# EPS32-v2.net
KiCad netlist of a schematic drawn in EasyEDA Pro
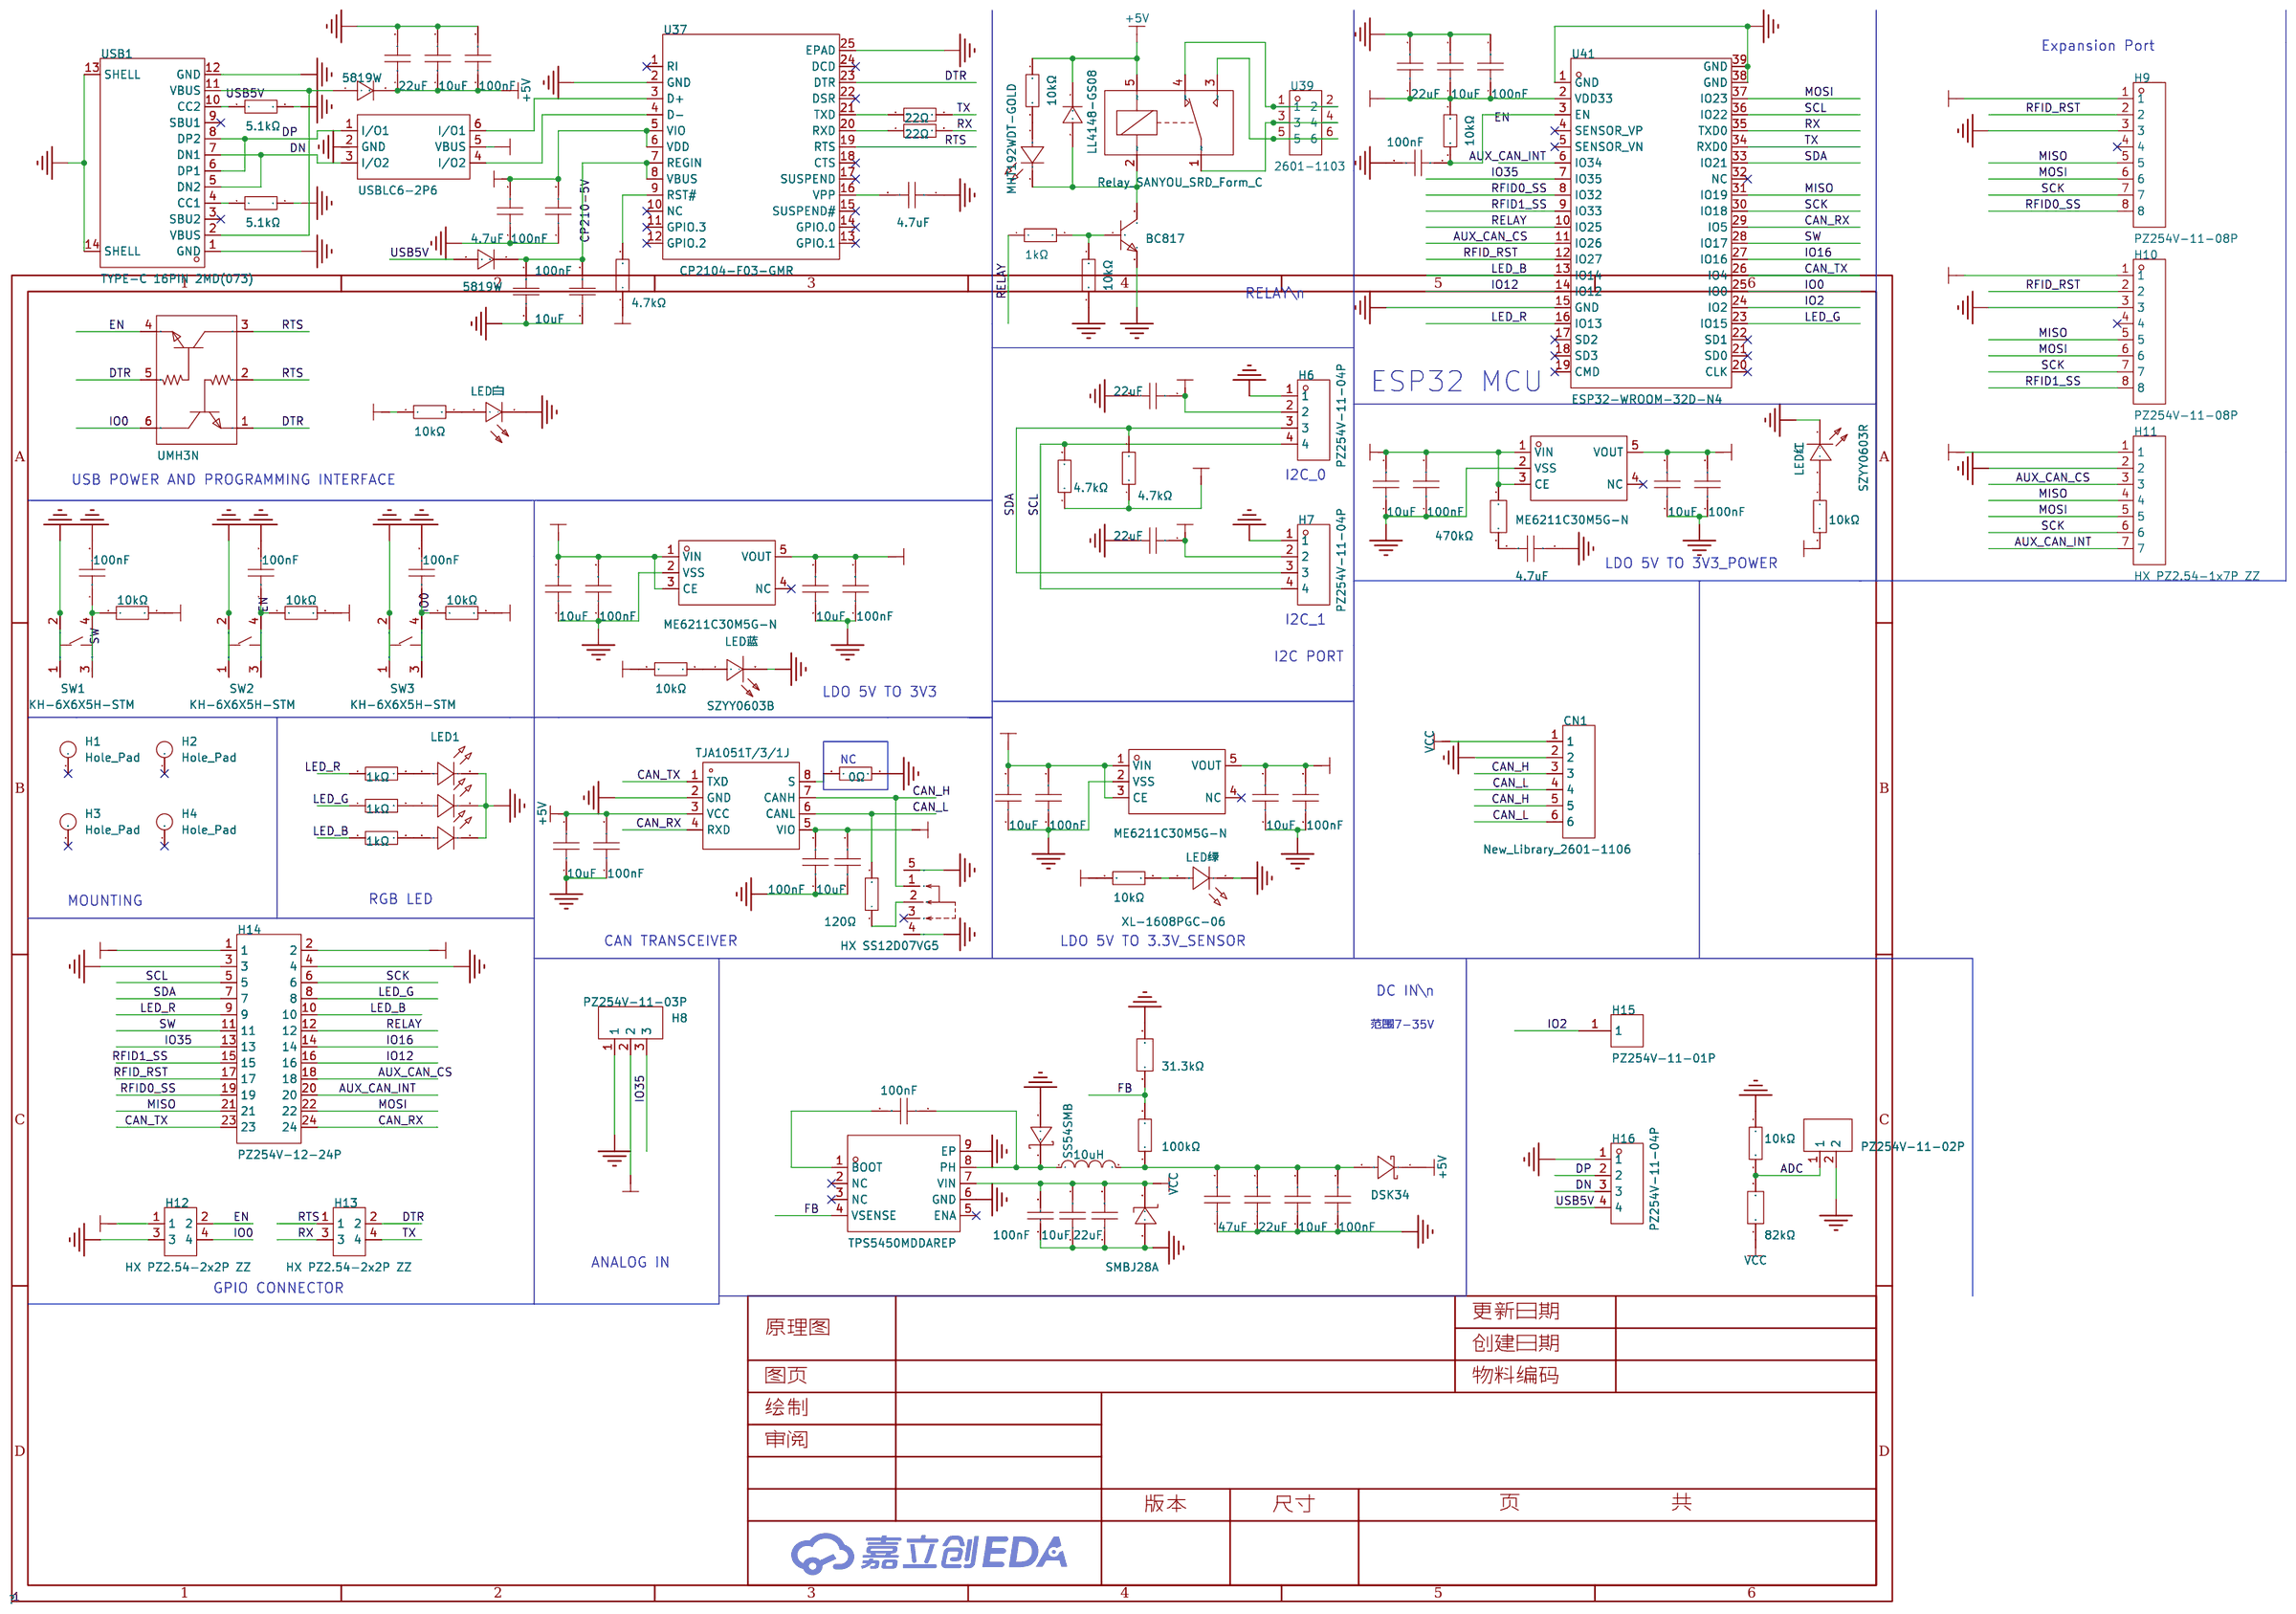
[diagram p0: schematic sheet]

(export (version "E")
  (design (tool "Eeschema 10.0.6"))
  (components
    (comp (ref "C1")
      (value "22uF")
      (footprint "easyedapro:C0805")
      (description "容值:22uF;精度:±20%;额定电压:35V;材质(温度系数):X5R;")
      (fields
        (field (name "Manufacturer Part") "CGA0805X5R226M350MT")
        (field (name "Manufacturer") "HRE(芯声)")
      )
      (libsource (lib "easyedapro") (part "CGA0805X5R226M350MT"))
    )
    (comp (ref "C2")
      (value "10uF")
      (footprint "easyedapro:C0603")
      (description "容值:10uF;精度:±20%;额定电压:25V;材质(温度系数):X5R;")
      (fields
        (field (name "Manufacturer Part") "CL10A106MA8NRNC")
        (field (name "Manufacturer") "SAMSUNG(三星)")
      )
      (libsource (lib "easyedapro") (part "CL10A106MA8NRNC"))
    )
    (comp (ref "C3")
      (value "100nF")
      (footprint "easyedapro:C0603")
      (description "容值:100nF;精度:±10%;额定电压:50V;温度系数:X7R;")
      (fields
        (field (name "Manufacturer Part") "CGA0603X7R104K500JT")
        (field (name "Manufacturer") "HRE(芯声)")
      )
      (libsource (lib "easyedapro") (part "CGA0603X7R104K500JT"))
    )
    (comp (ref "C6")
      (value "4.7uF")
      (footprint "easyedapro:C0603")
      (description "容值:4.7uF;精度:±10%;额定电压:25V;温度系数:X5R;")
      (fields
        (field (name "Manufacturer Part") "CGA0603X5R475K250JT")
        (field (name "Manufacturer") "HRE(芯声)")
      )
      (libsource (lib "easyedapro") (part "CGA0603X5R475K250JT"))
    )
    (comp (ref "C9")
      (value "100nF")
      (footprint "easyedapro:C0603")
      (description "容值:100nF;精度:±10%;额定电压:50V;温度系数:X7R;")
      (fields
        (field (name "Manufacturer Part") "CGA0603X7R104K500JT")
        (field (name "Manufacturer") "HRE(芯声)")
      )
      (libsource (lib "easyedapro") (part "CGA0603X7R104K500JT"))
    )
    (comp (ref "C10")
      (value "100nF")
      (footprint "easyedapro:C0603")
      (description "容值:100nF;精度:±10%;额定电压:50V;温度系数:X7R;")
      (fields
        (field (name "Manufacturer Part") "CGA0603X7R104K500JT")
        (field (name "Manufacturer") "HRE(芯声)")
      )
      (libsource (lib "easyedapro") (part "CGA0603X7R104K500JT"))
    )
    (comp (ref "C11")
      (value "100nF")
      (footprint "easyedapro:C0603")
      (description "容值:100nF;精度:±10%;额定电压:50V;温度系数:X7R;")
      (fields
        (field (name "Manufacturer Part") "CGA0603X7R104K500JT")
        (field (name "Manufacturer") "HRE(芯声)")
      )
      (libsource (lib "easyedapro") (part "CGA0603X7R104K500JT"))
    )
    (comp (ref "C351")
      (value "10uF")
      (footprint "easyedapro:C0603")
      (description "容值:10uF;精度:±20%;额定电压:25V;材质(温度系数):X5R;")
      (fields
        (field (name "Manufacturer Part") "CL10A106MA8NRNC")
        (field (name "Manufacturer") "SAMSUNG(三星)")
      )
      (libsource (lib "easyedapro") (part "CL10A106MA8NRNC"))
    )
    (comp (ref "C352")
      (value "10uF")
      (footprint "easyedapro:C0603")
      (description "容值:10uF;精度:±20%;额定电压:25V;材质(温度系数):X5R;")
      (fields
        (field (name "Manufacturer Part") "CL10A106MA8NRNC")
        (field (name "Manufacturer") "SAMSUNG(三星)")
      )
      (libsource (lib "easyedapro") (part "CL10A106MA8NRNC"))
    )
    (comp (ref "C353")
      (value "100nF")
      (footprint "easyedapro:C0603")
      (description "容值:100nF;精度:±10%;额定电压:50V;温度系数:X7R;")
      (fields
        (field (name "Manufacturer Part") "CGA0603X7R104K500JT")
        (field (name "Manufacturer") "HRE(芯声)")
      )
      (libsource (lib "easyedapro") (part "CGA0603X7R104K500JT"))
    )
    (comp (ref "C354")
      (value "100nF")
      (footprint "easyedapro:C0603")
      (description "容值:100nF;精度:±10%;额定电压:50V;温度系数:X7R;")
      (fields
        (field (name "Manufacturer Part") "CGA0603X7R104K500JT")
        (field (name "Manufacturer") "HRE(芯声)")
      )
      (libsource (lib "easyedapro") (part "CGA0603X7R104K500JT"))
    )
    (comp (ref "C355")
      (value "10uF")
      (footprint "easyedapro:C0603")
      (description "容值:10uF;精度:±20%;额定电压:25V;材质(温度系数):X5R;")
      (fields
        (field (name "Manufacturer Part") "CL10A106MA8NRNC")
        (field (name "Manufacturer") "SAMSUNG(三星)")
      )
      (libsource (lib "easyedapro") (part "CL10A106MA8NRNC"))
    )
    (comp (ref "C356")
      (value "100nF")
      (footprint "easyedapro:C0603")
      (description "容值:100nF;精度:±10%;额定电压:50V;温度系数:X7R;")
      (fields
        (field (name "Manufacturer Part") "CGA0603X7R104K500JT")
        (field (name "Manufacturer") "HRE(芯声)")
      )
      (libsource (lib "easyedapro") (part "CGA0603X7R104K500JT"))
    )
    (comp (ref "C357")
      (value "10uF")
      (footprint "easyedapro:C0603")
      (description "容值:10uF;精度:±20%;额定电压:25V;材质(温度系数):X5R;")
      (fields
        (field (name "Manufacturer Part") "CL10A106MA8NRNC")
        (field (name "Manufacturer") "SAMSUNG(三星)")
      )
      (libsource (lib "easyedapro") (part "CL10A106MA8NRNC"))
    )
    (comp (ref "C358")
      (value "100nF")
      (footprint "easyedapro:C0603")
      (description "容值:100nF;精度:±10%;额定电压:50V;温度系数:X7R;")
      (fields
        (field (name "Manufacturer Part") "CGA0603X7R104K500JT")
        (field (name "Manufacturer") "HRE(芯声)")
      )
      (libsource (lib "easyedapro") (part "CGA0603X7R104K500JT"))
    )
    (comp (ref "C359")
      (value "100nF")
      (footprint "easyedapro:C0603")
      (description "容值:100nF;精度:±10%;额定电压:50V;温度系数:X7R;")
      (fields
        (field (name "Manufacturer Part") "CGA0603X7R104K500JT")
        (field (name "Manufacturer") "HRE(芯声)")
      )
      (libsource (lib "easyedapro") (part "CGA0603X7R104K500JT"))
    )
    (comp (ref "C360")
      (value "4.7uF")
      (footprint "easyedapro:C0603")
      (description "容值:4.7uF;精度:±10%;额定电压:25V;温度系数:X5R;")
      (fields
        (field (name "Manufacturer Part") "CGA0603X5R475K250JT")
        (field (name "Manufacturer") "HRE(芯声)")
      )
      (libsource (lib "easyedapro") (part "CGA0603X5R475K250JT"))
    )
    (comp (ref "C361")
      (value "10uF")
      (footprint "easyedapro:C0603")
      (description "容值:10uF;精度:±20%;额定电压:25V;材质(温度系数):X5R;")
      (fields
        (field (name "Manufacturer Part") "CL10A106MA8NRNC")
        (field (name "Manufacturer") "SAMSUNG(三星)")
      )
      (libsource (lib "easyedapro") (part "CL10A106MA8NRNC"))
    )
    (comp (ref "C362")
      (value "100nF")
      (footprint "easyedapro:C0603")
      (description "容值:100nF;精度:±10%;额定电压:50V;温度系数:X7R;")
      (fields
        (field (name "Manufacturer Part") "CGA0603X7R104K500JT")
        (field (name "Manufacturer") "HRE(芯声)")
      )
      (libsource (lib "easyedapro") (part "CGA0603X7R104K500JT"))
    )
    (comp (ref "C363")
      (value "22uF")
      (footprint "easyedapro:C0805")
      (description "容值:22uF;精度:±20%;额定电压:35V;材质(温度系数):X5R;")
      (fields
        (field (name "Manufacturer Part") "CGA0805X5R226M350MT")
        (field (name "Manufacturer") "HRE(芯声)")
      )
      (libsource (lib "easyedapro") (part "CGA0805X5R226M350MT"))
    )
    (comp (ref "C364")
      (value "22uF")
      (footprint "easyedapro:C0805")
      (description "容值:22uF;精度:±20%;额定电压:35V;材质(温度系数):X5R;")
      (fields
        (field (name "Manufacturer Part") "CGA0805X5R226M350MT")
        (field (name "Manufacturer") "HRE(芯声)")
      )
      (libsource (lib "easyedapro") (part "CGA0805X5R226M350MT"))
    )
    (comp (ref "C369")
      (value "10uF")
      (footprint "easyedapro:C0603")
      (description "容值:10uF;精度:±20%;额定电压:25V;材质(温度系数):X5R;")
      (fields
        (field (name "Manufacturer Part") "CL10A106MA8NRNC")
        (field (name "Manufacturer") "SAMSUNG(三星)")
      )
      (libsource (lib "easyedapro") (part "CL10A106MA8NRNC"))
    )
    (comp (ref "C370")
      (value "10uF")
      (footprint "easyedapro:C0603")
      (description "容值:10uF;精度:±20%;额定电压:25V;材质(温度系数):X5R;")
      (fields
        (field (name "Manufacturer Part") "CL10A106MA8NRNC")
        (field (name "Manufacturer") "SAMSUNG(三星)")
      )
      (libsource (lib "easyedapro") (part "CL10A106MA8NRNC"))
    )
    (comp (ref "C371")
      (value "100nF")
      (footprint "easyedapro:C0603")
      (description "容值:100nF;精度:±10%;额定电压:50V;温度系数:X7R;")
      (fields
        (field (name "Manufacturer Part") "CGA0603X7R104K500JT")
        (field (name "Manufacturer") "HRE(芯声)")
      )
      (libsource (lib "easyedapro") (part "CGA0603X7R104K500JT"))
    )
    (comp (ref "C372")
      (value "100nF")
      (footprint "easyedapro:C0603")
      (description "容值:100nF;精度:±10%;额定电压:50V;温度系数:X7R;")
      (fields
        (field (name "Manufacturer Part") "CGA0603X7R104K500JT")
        (field (name "Manufacturer") "HRE(芯声)")
      )
      (libsource (lib "easyedapro") (part "CGA0603X7R104K500JT"))
    )
    (comp (ref "C373")
      (value "10uF")
      (footprint "easyedapro:C0603")
      (description "容值:10uF;精度:±20%;额定电压:25V;材质(温度系数):X5R;")
      (fields
        (field (name "Manufacturer Part") "CL10A106MA8NRNC")
        (field (name "Manufacturer") "SAMSUNG(三星)")
      )
      (libsource (lib "easyedapro") (part "CL10A106MA8NRNC"))
    )
    (comp (ref "C374")
      (value "100nF")
      (footprint "easyedapro:C0603")
      (description "容值:100nF;精度:±10%;额定电压:50V;温度系数:X7R;")
      (fields
        (field (name "Manufacturer Part") "CGA0603X7R104K500JT")
        (field (name "Manufacturer") "HRE(芯声)")
      )
      (libsource (lib "easyedapro") (part "CGA0603X7R104K500JT"))
    )
    (comp (ref "C375")
      (value "100nF")
      (footprint "easyedapro:C0603")
      (description "容值:100nF;精度:±10%;额定电压:50V;温度系数:X7R;")
      (fields
        (field (name "Manufacturer Part") "CGA0603X7R104K500JT")
        (field (name "Manufacturer") "HRE(芯声)")
      )
      (libsource (lib "easyedapro") (part "CGA0603X7R104K500JT"))
    )
    (comp (ref "C376")
      (value "10uF")
      (footprint "easyedapro:C0603")
      (description "容值:10uF;精度:±20%;额定电压:25V;材质(温度系数):X5R;")
      (fields
        (field (name "Manufacturer Part") "CL10A106MA8NRNC")
        (field (name "Manufacturer") "SAMSUNG(三星)")
      )
      (libsource (lib "easyedapro") (part "CL10A106MA8NRNC"))
    )
    (comp (ref "C377")
      (value "22uF")
      (footprint "easyedapro:C0805")
      (description "容值:22uF;精度:±20%;额定电压:35V;材质(温度系数):X5R;")
      (fields
        (field (name "Manufacturer Part") "CGA0805X5R226M350MT")
        (field (name "Manufacturer") "HRE(芯声)")
      )
      (libsource (lib "easyedapro") (part "CGA0805X5R226M350MT"))
    )
    (comp (ref "C378")
      (value "10uF")
      (footprint "easyedapro:C0603")
      (description "容值:10uF;精度:±20%;额定电压:25V;材质(温度系数):X5R;")
      (fields
        (field (name "Manufacturer Part") "CL10A106MA8NRNC")
        (field (name "Manufacturer") "SAMSUNG(三星)")
      )
      (libsource (lib "easyedapro") (part "CL10A106MA8NRNC"))
    )
    (comp (ref "C379")
      (value "100nF")
      (footprint "easyedapro:C0603")
      (description "容值:100nF;精度:±10%;额定电压:50V;温度系数:X7R;")
      (fields
        (field (name "Manufacturer Part") "CGA0603X7R104K500JT")
        (field (name "Manufacturer") "HRE(芯声)")
      )
      (libsource (lib "easyedapro") (part "CGA0603X7R104K500JT"))
    )
    (comp (ref "C380")
      (value "100nF")
      (footprint "easyedapro:C0603")
      (description "容值:100nF;精度:±10%;额定电压:50V;温度系数:X7R;")
      (fields
        (field (name "Manufacturer Part") "CGA0603X7R104K500JT")
        (field (name "Manufacturer") "HRE(芯声)")
      )
      (libsource (lib "easyedapro") (part "CGA0603X7R104K500JT"))
    )
    (comp (ref "C382")
      (value "10uF")
      (footprint "easyedapro:C1206")
      (description "容值:10uF;精度:±10%;额定电压:50V;温度系数:X5R;")
      (fields
        (field (name "Manufacturer Part") "HGC1206R5106K500NSPJ")
        (field (name "Manufacturer") "Chinocera(华瓷)")
      )
      (libsource (lib "easyedapro") (part "HGC1206R5106K500NSPJ"))
    )
    (comp (ref "C383")
      (value "22uF")
      (footprint "easyedapro:C1206")
      (description "容值:22uF;精度:±20%;额定电压:35V;温度系数:X5R;")
      (fields
        (field (name "Manufacturer Part") "CGA1206X5R226M350NT")
        (field (name "Manufacturer") "HRE(芯声)")
      )
      (libsource (lib "easyedapro") (part "CGA1206X5R226M350NT"))
    )
    (comp (ref "C384")
      (value "100nF")
      (footprint "easyedapro:C1206")
      (description "容值:100nF;精度:±10%;额定电压:50V;材质(温度系数):X7R;")
      (fields
        (field (name "Manufacturer Part") "CL31B104KBCNNNC")
        (field (name "Manufacturer") "SAMSUNG(三星)")
      )
      (libsource (lib "easyedapro") (part "CL31B104KBCNNNC"))
    )
    (comp (ref "C385")
      (value "47uF")
      (footprint "easyedapro:C1206")
      (description "容值:47uF;精度:±20%;额定电压:25V;温度系数:X5R;")
      (fields
        (field (name "Manufacturer Part") "HGC1206R5476M250NSPJ")
        (field (name "Manufacturer") "Chinocera(华瓷)")
      )
      (libsource (lib "easyedapro") (part "HGC1206R5476M250NSPJ"))
    )
    (comp (ref "C386")
      (value "22uF")
      (footprint "easyedapro:C0805")
      (description "容值:22uF;精度:±20%;额定电压:35V;材质(温度系数):X5R;")
      (fields
        (field (name "Manufacturer Part") "CGA0805X5R226M350MT")
        (field (name "Manufacturer") "HRE(芯声)")
      )
      (libsource (lib "easyedapro") (part "CGA0805X5R226M350MT"))
    )
    (comp (ref "C387")
      (value "10uF")
      (footprint "easyedapro:C0603")
      (description "容值:10uF;精度:±20%;额定电压:25V;材质(温度系数):X5R;")
      (fields
        (field (name "Manufacturer Part") "CL10A106MA8NRNC")
        (field (name "Manufacturer") "SAMSUNG(三星)")
      )
      (libsource (lib "easyedapro") (part "CL10A106MA8NRNC"))
    )
    (comp (ref "C388")
      (value "100nF")
      (footprint "easyedapro:C0603")
      (description "容值:100nF;精度:±10%;额定电压:50V;温度系数:X7R;")
      (fields
        (field (name "Manufacturer Part") "CGA0603X7R104K500JT")
        (field (name "Manufacturer") "HRE(芯声)")
      )
      (libsource (lib "easyedapro") (part "CGA0603X7R104K500JT"))
    )
    (comp (ref "C389")
      (value "100nF")
      (footprint "easyedapro:C0603")
      (description "容值:100nF;精度:±10%;额定电压:50V;温度系数:X7R;")
      (fields
        (field (name "Manufacturer Part") "CGA0603X7R104K500JT")
        (field (name "Manufacturer") "HRE(芯声)")
      )
      (libsource (lib "easyedapro") (part "CGA0603X7R104K500JT"))
    )
    (comp (ref "C390")
      (value "4.7uF")
      (footprint "easyedapro:C0603")
      (description "容值:4.7uF;精度:±10%;额定电压:25V;温度系数:X5R;")
      (fields
        (field (name "Manufacturer Part") "CGA0603X5R475K250JT")
        (field (name "Manufacturer") "HRE(芯声)")
      )
      (libsource (lib "easyedapro") (part "CGA0603X5R475K250JT"))
    )
    (comp (ref "CN1")
      (value "New_Library_2601-1106")
      (footprint "easyedapro:CONN-TH_2601-1106")
      (fields (field (name "Manufacturer Part") "2601-1106"))
      (libsource (lib "easyedapro") (part "2601-1106"))
    )
    (comp (ref "D1")
      (value "USBLC6-2P6")
      (footprint "easyedapro:SOT-666-6_L1.6-W1.2-P0.50-LS1.6-BL")
      (description "极性:单向;反向截止电压(Vrwm):5V;最大钳位电压:14V;峰值脉冲电流(Ipp):5.5A;峰值脉冲功率(Ppp):80W;击穿电压:6V;")
      (fields (field (name "Manufacturer") "TECH PUBLIC(台舟)"))
      (libsource (lib "easyedapro") (part "USBLC6-2P6_C2827693"))
    )
    (comp (ref "D2")
      (value "5819W")
      (footprint "easyedapro:SOD-123_L2.7-W1.6-LS3.7-FD")
      (description "正向压降(Vf):900mV@3A;直流反向耐压(Vr):40V;整流电流:1A;")
      (fields (field (name "Manufacturer") "MOT(仁懋)"))
      (libsource (lib "easyedapro") (part "5819W"))
    )
    (comp (ref "D3")
      (value "LL4148-GS08")
      (footprint "easyedapro:SOD-80_L3.5-W1.5-RD")
      (description "二极管配置:-;正向压降(Vf):860mV@50mA;直流反向耐压(Vr):75V;整流电流:300mA;反向恢复时间(Trr):-;")
      (fields (field (name "Manufacturer") "VISHAY(威世)"))
      (libsource (lib "easyedapro") (part "LL4148-GS08"))
    )
    (comp (ref "D5")
      (value "SS54SMB")
      (footprint "easyedapro:SMB_L4.6-W3.6-LS5.3-RD")
      (description "schottky,5A 40V VF&lt;0.55V DO-214AA SMB")
      (fields (field (name "Manufacturer") "BORN(伯恩半导体)"))
      (libsource (lib "easyedapro") (part "SS54SMB"))
    )
    (comp (ref "D6")
      (value "SMBJ28A")
      (footprint "easyedapro:SMB_L4.6-W3.6-LS5.3-L-FD")
      (description "极性:Unidirectional;峰值脉冲电流（10/1000us）:13.2A;箝位电压:45.4V;击穿电压（最小值）:31.1V;反向关断电压（典型值）:28V;")
      (fields (field (name "Manufacturer") "JJW(捷捷微)"))
      (libsource (lib "easyedapro") (part "SMBJ28A_C356769"))
    )
    (comp (ref "D7")
      (value "DSK34")
      (footprint "easyedapro:SOD-123FL_L2.7-W1.8-LS3.8-RD")
      (description "二极管配置:独立式;正向压降(Vf):550mV@3A;直流反向耐压(Vr):40V;平均整流电流(Io):3A;")
      (fields (field (name "Manufacturer") "宏迦橙"))
      (libsource (lib "easyedapro") (part "DSK34_C7502709"))
    )
    (comp (ref "D8")
      (value "5819W")
      (footprint "easyedapro:SOD-123_L2.7-W1.6-LS3.7-FD")
      (description "正向压降(Vf):900mV@3A;直流反向耐压(Vr):40V;整流电流:1A;")
      (fields (field (name "Manufacturer") "MOT(仁懋)"))
      (libsource (lib "easyedapro") (part "5819W"))
    )
    (comp (ref "H1")
      (value "Hole_Pad")
      (footprint "easyedapro:MountingHole:MountingHole_3.2mm_M3_Pad_Via")
      (description "Mounting Hole with connection")
      (libsource (lib "easyedapro") (part "Mechanical_MountingHole_Pad"))
    )
    (comp (ref "H2")
      (value "Hole_Pad")
      (footprint "easyedapro:MountingHole:MountingHole_3.2mm_M3_Pad_Via")
      (description "Mounting Hole with connection")
      (libsource (lib "easyedapro") (part "Mechanical_MountingHole_Pad"))
    )
    (comp (ref "H3")
      (value "Hole_Pad")
      (footprint "easyedapro:MountingHole:MountingHole_3.2mm_M3_Pad_Via")
      (description "Mounting Hole with connection")
      (libsource (lib "easyedapro") (part "Mechanical_MountingHole_Pad"))
    )
    (comp (ref "H4")
      (value "Hole_Pad")
      (footprint "easyedapro:MountingHole:MountingHole_3.2mm_M3_Pad_Via")
      (description "Mounting Hole with connection")
      (libsource (lib "easyedapro") (part "Mechanical_MountingHole_Pad"))
    )
    (comp (ref "H6")
      (value "PZ254V-11-04P")
      (footprint "easyedapro:HDR-TH_4P-P2.54-V-M")
      (fields (field (name "Manufacturer") "XFCN(兴飞)"))
      (libsource (lib "easyedapro") (part "PZ254V-11-04P_C2691448"))
    )
    (comp (ref "H7")
      (value "PZ254V-11-04P")
      (footprint "easyedapro:HDR-TH_4P-P2.54-V-M")
      (fields (field (name "Manufacturer") "XFCN(兴飞)"))
      (libsource (lib "easyedapro") (part "PZ254V-11-04P_C2691448"))
    )
    (comp (ref "H8")
      (value "PZ254V-11-03P")
      (footprint "easyedapro:HDR-TH_3P-P2.54-V-M")
      (fields (field (name "Manufacturer") "XFCN(兴飞)"))
      (libsource (lib "easyedapro") (part "PZ254V-11-03P_C2937625"))
    )
    (comp (ref "H9")
      (value "PZ254V-11-08P")
      (footprint "easyedapro:HDR-TH_8P-P2.54-V-M")
      (fields (field (name "Manufacturer") "XFCN(兴飞)"))
      (libsource (lib "easyedapro") (part "PZ254V-11-08P"))
    )
    (comp (ref "H10")
      (value "PZ254V-11-08P")
      (footprint "easyedapro:HDR-TH_8P-P2.54-V-M")
      (fields (field (name "Manufacturer") "XFCN(兴飞)"))
      (libsource (lib "easyedapro") (part "PZ254V-11-08P"))
    )
    (comp (ref "H11")
      (value "HX PZ2.54-1x7P ZZ")
      (footprint "easyedapro:HDR-TH_7P-P2.54-V-M")
      (fields (field (name "Manufacturer") "hanxia(韩下)"))
      (libsource (lib "easyedapro") (part "HX PZ2.54-1X7P ZZ"))
    )
    (comp (ref "H12")
      (value "HX PZ2.54-2x2P ZZ")
      (footprint "easyedapro:HDR-TH_HX-PZ2.54-2X2P-ZZ")
      (fields (field (name "Manufacturer") "hanxia(韩下)"))
      (libsource (lib "easyedapro") (part "HX PZ2.54-2X2P ZZ"))
    )
    (comp (ref "H13")
      (value "HX PZ2.54-2x2P ZZ")
      (footprint "easyedapro:HDR-TH_HX-PZ2.54-2X2P-ZZ")
      (fields (field (name "Manufacturer") "hanxia(韩下)"))
      (libsource (lib "easyedapro") (part "HX PZ2.54-2X2P ZZ"))
    )
    (comp (ref "H14")
      (value "PZ254V-12-24P")
      (footprint "easyedapro:HDR-TH_24P-P2.54-V-M-R2-C12-S2.54")
      (fields (field (name "Manufacturer") "XFCN(兴飞)"))
      (libsource (lib "easyedapro") (part "PZ254V-12-24P"))
    )
    (comp (ref "H15")
      (value "PZ254V-11-01P")
      (footprint "easyedapro:HDR-TH_1P-P2.54-V-M")
      (fields (field (name "Manufacturer") "XFCN(兴飞)"))
      (libsource (lib "easyedapro") (part "PZ254V-11-01P"))
    )
    (comp (ref "H16")
      (value "PZ254V-11-04P")
      (footprint "easyedapro:HDR-TH_4P-P2.54-V-M")
      (fields (field (name "Manufacturer") "XFCN(兴飞)"))
      (libsource (lib "easyedapro") (part "PZ254V-11-04P_C2691448"))
    )
    (comp (ref "H17")
      (value "PZ254V-11-02P")
      (footprint "easyedapro:HDR-TH_2P-P2.54-V-M")
      (fields (field (name "Manufacturer") "XFCN(兴飞)"))
      (libsource (lib "easyedapro") (part "PZ254V-11-02P"))
    )
    (comp (ref "K1")
      (value "SANYOU_SRD_Form_C")
      (footprint "easyedapro:Relay_THT:Relay_SPDT_SANYOU_SRD_Series_Form_C")
      (libsource (lib "easyedapro") (part "Relay_SANYOU_SRD_Form_C"))
    )
    (comp (ref "L12")
      (value "10uH")
      (footprint "easyedapro:IND-SMD_L5.4-W5.2_FXL0530")
      (description "电感值:10uH;精度:±20%;额定电流:3.2A;饱和电流(Isat):3.5A;类型:一体成型电感;")
      (fields (field (name "Manufacturer Part") "FXL0530-100-M") (field (name "Manufacturer") "cjiang(长江微电)"))
      (libsource (lib "easyedapro") (part "FXL0530-100-M"))
    )
    (comp (ref "LED1")
      (value "TC5050RGBF08-3CJH-AF53A")
      (footprint "easyedapro:LED-SMD_6P-L5.0-W5.0-TL_TC5050RGBF08")
      (description "5050RGB，0.2W 20mA")
      (fields (field (name "Manufacturer") "TCWIN(天成)"))
      (libsource (lib "easyedapro") (part "TC5050RGBF08-3CJH-AF53A"))
    )
    (comp (ref "LED白")
      (value "NCD0603W1")
      (footprint "easyedapro:LED0603-RD")
      (fields (field (name "Manufacturer") "国星光电"))
      (libsource (lib "easyedapro") (part "NCD0603W1"))
    )
    (comp (ref "LED红")
      (value "SZYY0603R")
      (footprint "easyedapro:LED0603-R-RD")
      (fields (field (name "Manufacturer") "yongyu(永裕光电)"))
      (libsource (lib "easyedapro") (part "SZYY0603R"))
    )
    (comp (ref "LED绿")
      (value "XL-1608PGC-06")
      (footprint "easyedapro:LED0603-RD_GREEN")
      (fields (field (name "Manufacturer") "XINGLIGHT(成兴光)"))
      (libsource (lib "easyedapro") (part "XL-1608PGC-06"))
    )
    (comp (ref "LED蓝")
      (value "SZYY0603B")
      (footprint "easyedapro:LED0603-R-RD_BLUE")
      (fields (field (name "Manufacturer") "yongyu(永裕光电)"))
      (libsource (lib "easyedapro") (part "SZYY0603B"))
    )
    (comp (ref "Q1")
      (value "UMH3N")
      (footprint "easyedapro:SC-70-6_L2.2-W1.3-P0.65-LS2.1-BR")
      (description "晶体管类型:-;集射极击穿电压(Vceo):50V;集电极电流(Ic):100mA;耗散功率(Pd):150mW;直流电流增益(hFE):100@1mA,5V;")
      (fields (field (name "Manufacturer") "CJ(江苏长电/长晶)"))
      (libsource (lib "easyedapro") (part "UMH3N"))
    )
    (comp (ref "Q2")
      (value "BC817")
      (footprint "easyedapro:SOT-23-3_L2.9-W1.3-P1.90-LS2.4-BR")
      (description "晶体管类型:NPN;集电极电流(Ic):500mA;集射极击穿电压(Vceo):45V;耗散功率(Pd):300mW;直流电流增益(hFE):-;")
      (fields (field (name "Manufacturer") "JSMSEMI(杰盛微)"))
      (libsource (lib "easyedapro") (part "BC817_C916383"))
    )
    (comp (ref "R1")
      (value "5.1kΩ")
      (footprint "easyedapro:R0603")
      (description "电阻类型:厚膜电阻;阻值:5.1kΩ;精度:±1%;功率:100mW;最大工作电压:75V;温度系数:±100ppm/°C;")
      (fields
        (field (name "Manufacturer Part") "0603WAF5101T5E")
        (field (name "Manufacturer") "UNI-ROYAL(厚声)")
      )
      (libsource (lib "easyedapro") (part "0603WAF5101T5E"))
    )
    (comp (ref "R2")
      (value "5.1kΩ")
      (footprint "easyedapro:R0603")
      (description "电阻类型:厚膜电阻;阻值:5.1kΩ;精度:±1%;功率:100mW;最大工作电压:75V;温度系数:±100ppm/°C;")
      (fields
        (field (name "Manufacturer Part") "0603WAF5101T5E")
        (field (name "Manufacturer") "UNI-ROYAL(厚声)")
      )
      (libsource (lib "easyedapro") (part "0603WAF5101T5E"))
    )
    (comp (ref "R4")
      (value "22Ω")
      (footprint "easyedapro:R0603")
      (description "电阻类型:厚膜电阻;阻值:22Ω;精度:±1%;功率:100mW;最大工作电压:75V;温度系数:±100ppm/°C;")
      (fields
        (field (name "Manufacturer Part") "0603WAF220JT5E")
        (field (name "Manufacturer") "UNI-ROYAL(厚声)")
      )
      (libsource (lib "easyedapro") (part "0603WAF220JT5E"))
    )
    (comp (ref "R5")
      (value "22Ω")
      (footprint "easyedapro:R0603")
      (description "电阻类型:厚膜电阻;阻值:22Ω;精度:±1%;功率:100mW;最大工作电压:75V;温度系数:±100ppm/°C;")
      (fields
        (field (name "Manufacturer Part") "0603WAF220JT5E")
        (field (name "Manufacturer") "UNI-ROYAL(厚声)")
      )
      (libsource (lib "easyedapro") (part "0603WAF220JT5E"))
    )
    (comp (ref "R7")
      (value "10kΩ")
      (footprint "easyedapro:R0603")
      (description "电阻类型:厚膜电阻;阻值:10kΩ;精度:±1%;功率:100mW;工作电压:75V;温度系数:±100ppm/°C;")
      (fields
        (field (name "Manufacturer Part") "0603WAF1002T5E")
        (field (name "Manufacturer") "UNI-ROYAL(厚声)")
      )
      (libsource (lib "easyedapro") (part "0603WAF1002T5E"))
    )
    (comp (ref "R8")
      (value "10kΩ")
      (footprint "easyedapro:R0603")
      (description "电阻类型:厚膜电阻;阻值:10kΩ;精度:±1%;功率:100mW;工作电压:75V;温度系数:±100ppm/°C;")
      (fields
        (field (name "Manufacturer Part") "0603WAF1002T5E")
        (field (name "Manufacturer") "UNI-ROYAL(厚声)")
      )
      (libsource (lib "easyedapro") (part "0603WAF1002T5E"))
    )
    (comp (ref "R9")
      (value "10kΩ")
      (footprint "easyedapro:R0603")
      (description "电阻类型:厚膜电阻;阻值:10kΩ;精度:±1%;功率:100mW;工作电压:75V;温度系数:±100ppm/°C;")
      (fields
        (field (name "Manufacturer Part") "0603WAF1002T5E")
        (field (name "Manufacturer") "UNI-ROYAL(厚声)")
      )
      (libsource (lib "easyedapro") (part "0603WAF1002T5E"))
    )
    (comp (ref "R10")
      (value "10kΩ")
      (footprint "easyedapro:R0603")
      (description "电阻类型:厚膜电阻;阻值:10kΩ;精度:±1%;功率:100mW;工作电压:75V;温度系数:±100ppm/°C;")
      (fields
        (field (name "Manufacturer Part") "0603WAF1002T5E")
        (field (name "Manufacturer") "UNI-ROYAL(厚声)")
      )
      (libsource (lib "easyedapro") (part "0603WAF1002T5E"))
    )
    (comp (ref "R11")
      (value "10kΩ")
      (footprint "easyedapro:R0603")
      (description "电阻类型:厚膜电阻;阻值:10kΩ;精度:±1%;功率:100mW;工作电压:75V;温度系数:±100ppm/°C;")
      (fields
        (field (name "Manufacturer Part") "0603WAF1002T5E")
        (field (name "Manufacturer") "UNI-ROYAL(厚声)")
      )
      (libsource (lib "easyedapro") (part "0603WAF1002T5E"))
    )
    (comp (ref "R12")
      (value "1kΩ")
      (footprint "easyedapro:R0603")
      (description "电阻类型:厚膜电阻;阻值:1kΩ;精度:±1%;功率:100mW;最大工作电压:75V;温度系数:±100ppm/°C;")
      (fields
        (field (name "Manufacturer Part") "0603WAF1001T5E")
        (field (name "Manufacturer") "UNI-ROYAL(厚声)")
      )
      (libsource (lib "easyedapro") (part "0603WAF1001T5E"))
    )
    (comp (ref "R13")
      (value "1kΩ")
      (footprint "easyedapro:R0603")
      (description "电阻类型:厚膜电阻;阻值:1kΩ;精度:±1%;功率:100mW;最大工作电压:75V;温度系数:±100ppm/°C;")
      (fields
        (field (name "Manufacturer Part") "0603WAF1001T5E")
        (field (name "Manufacturer") "UNI-ROYAL(厚声)")
      )
      (libsource (lib "easyedapro") (part "0603WAF1001T5E"))
    )
    (comp (ref "R14")
      (value "1kΩ")
      (footprint "easyedapro:R0603")
      (description "电阻类型:厚膜电阻;阻值:1kΩ;精度:±1%;功率:100mW;最大工作电压:75V;温度系数:±100ppm/°C;")
      (fields
        (field (name "Manufacturer Part") "0603WAF1001T5E")
        (field (name "Manufacturer") "UNI-ROYAL(厚声)")
      )
      (libsource (lib "easyedapro") (part "0603WAF1001T5E"))
    )
    (comp (ref "R15")
      (value "0Ω")
      (footprint "easyedapro:R0603")
      (description "电阻类型:厚膜电阻;阻值:0Ω;精度:±1%;功率:100mW;最大工作电压:75V;")
      (fields
        (field (name "Manufacturer Part") "0603WAF0000T5E")
        (field (name "Manufacturer") "UNI-ROYAL(厚声)")
      )
      (libsource (lib "easyedapro") (part "0603WAF0000T5E"))
    )
    (comp (ref "R17")
      (value "4.7kΩ")
      (footprint "easyedapro:R0603")
      (description "电阻类型:厚膜电阻;阻值:4.7kΩ;精度:±1%;功率:100mW;最大工作电压:75V;温度系数:±100ppm/°C;")
      (fields
        (field (name "Manufacturer Part") "0603WAF4701T5E")
        (field (name "Manufacturer") "UNI-ROYAL(厚声)")
      )
      (libsource (lib "easyedapro") (part "0603WAF4701T5E"))
    )
    (comp (ref "R18")
      (value "10kΩ")
      (footprint "easyedapro:R0603")
      (description "电阻类型:厚膜电阻;阻值:10kΩ;精度:±1%;功率:100mW;工作电压:75V;温度系数:±100ppm/°C;")
      (fields
        (field (name "Manufacturer Part") "0603WAF1002T5E")
        (field (name "Manufacturer") "UNI-ROYAL(厚声)")
      )
      (libsource (lib "easyedapro") (part "0603WAF1002T5E"))
    )
    (comp (ref "R19")
      (value "10kΩ")
      (footprint "easyedapro:R0603")
      (description "电阻类型:厚膜电阻;阻值:10kΩ;精度:±1%;功率:100mW;工作电压:75V;温度系数:±100ppm/°C;")
      (fields
        (field (name "Manufacturer Part") "0603WAF1002T5E")
        (field (name "Manufacturer") "UNI-ROYAL(厚声)")
      )
      (libsource (lib "easyedapro") (part "0603WAF1002T5E"))
    )
    (comp (ref "R20")
      (value "1kΩ")
      (footprint "easyedapro:R0603")
      (description "电阻类型:厚膜电阻;阻值:1kΩ;精度:±1%;功率:100mW;最大工作电压:75V;温度系数:±100ppm/°C;")
      (fields
        (field (name "Manufacturer Part") "0603WAF1001T5E")
        (field (name "Manufacturer") "UNI-ROYAL(厚声)")
      )
      (libsource (lib "easyedapro") (part "0603WAF1001T5E"))
    )
    (comp (ref "R21")
      (value "4.7kΩ")
      (footprint "easyedapro:R0603")
      (description "电阻类型:厚膜电阻;阻值:4.7kΩ;精度:±1%;功率:100mW;最大工作电压:75V;温度系数:±100ppm/°C;")
      (fields
        (field (name "Manufacturer Part") "0603WAF4701T5E")
        (field (name "Manufacturer") "UNI-ROYAL(厚声)")
      )
      (libsource (lib "easyedapro") (part "0603WAF4701T5E"))
    )
    (comp (ref "R22")
      (value "4.7kΩ")
      (footprint "easyedapro:R0603")
      (description "电阻类型:厚膜电阻;阻值:4.7kΩ;精度:±1%;功率:100mW;最大工作电压:75V;温度系数:±100ppm/°C;")
      (fields
        (field (name "Manufacturer Part") "0603WAF4701T5E")
        (field (name "Manufacturer") "UNI-ROYAL(厚声)")
      )
      (libsource (lib "easyedapro") (part "0603WAF4701T5E"))
    )
    (comp (ref "R23")
      (value "10kΩ")
      (footprint "easyedapro:R0603")
      (description "电阻类型:厚膜电阻;阻值:10kΩ;精度:±1%;功率:100mW;工作电压:75V;温度系数:±100ppm/°C;")
      (fields
        (field (name "Manufacturer Part") "0603WAF1002T5E")
        (field (name "Manufacturer") "UNI-ROYAL(厚声)")
      )
      (libsource (lib "easyedapro") (part "0603WAF1002T5E"))
    )
    (comp (ref "R24")
      (value "10kΩ")
      (footprint "easyedapro:R0603")
      (description "电阻类型:厚膜电阻;阻值:10kΩ;精度:±1%;功率:100mW;工作电压:75V;温度系数:±100ppm/°C;")
      (fields
        (field (name "Manufacturer Part") "0603WAF1002T5E")
        (field (name "Manufacturer") "UNI-ROYAL(厚声)")
      )
      (libsource (lib "easyedapro") (part "0603WAF1002T5E"))
    )
    (comp (ref "R25")
      (value "10kΩ")
      (footprint "easyedapro:R0603")
      (description "电阻类型:厚膜电阻;阻值:10kΩ;精度:±1%;功率:100mW;工作电压:75V;温度系数:±100ppm/°C;")
      (fields
        (field (name "Manufacturer Part") "0603WAF1002T5E")
        (field (name "Manufacturer") "UNI-ROYAL(厚声)")
      )
      (libsource (lib "easyedapro") (part "0603WAF1002T5E"))
    )
    (comp (ref "R30")
      (value "120Ω")
      (footprint "easyedapro:R0603")
      (description "电阻类型:厚膜电阻;阻值:120Ω;精度:±1%;功率:100mW;最大工作电压:75V;温度系数:±100ppm/°C;")
      (fields
        (field (name "Manufacturer Part") "0603WAF1200T5E")
        (field (name "Manufacturer") "UNI-ROYAL(厚声)")
      )
      (libsource (lib "easyedapro") (part "0603WAF1200T5E"))
    )
    (comp (ref "R31")
      (value "82kΩ")
      (footprint "easyedapro:R0603")
      (description "电阻类型:厚膜电阻;阻值:82kΩ;精度:±1%;功率:100mW;工作电压:75V;温度系数:±100ppm/°C;")
      (fields (field (name "Manufacturer Part") "FRC0603F8202TS") (field (name "Manufacturer") "FOJAN(富捷)"))
      (libsource (lib "easyedapro") (part "FRC0603F8202TS"))
    )
    (comp (ref "R32")
      (value "10kΩ")
      (footprint "easyedapro:R0603")
      (description "电阻类型:厚膜电阻;阻值:10kΩ;精度:±1%;功率:100mW;工作电压:75V;温度系数:±100ppm/°C;")
      (fields
        (field (name "Manufacturer Part") "0603WAF1002T5E")
        (field (name "Manufacturer") "UNI-ROYAL(厚声)")
      )
      (libsource (lib "easyedapro") (part "0603WAF1002T5E"))
    )
    (comp (ref "R34")
      (value "100kΩ")
      (footprint "easyedapro:R0603")
      (description "电阻类型:厚膜电阻;阻值:100kΩ;精度:±1%;功率:100mW;最大工作电压:75V;温度系数:±100ppm/°C;")
      (fields
        (field (name "Manufacturer Part") "0603WAF1003T5E")
        (field (name "Manufacturer") "UNI-ROYAL(厚声)")
      )
      (libsource (lib "easyedapro") (part "0603WAF1003T5E"))
    )
    (comp (ref "R35")
      (value "31.3kΩ")
      (footprint "easyedapro:R0603")
      (description "电阻类型:厚膜电阻;阻值:31.3kΩ;精度:±1%;功率:100mW;最大工作电压:75V;温度系数:±100ppm/°C;")
      (fields
        (field (name "Manufacturer Part") "0603WAF3132T5E")
        (field (name "Manufacturer") "UNI-ROYAL(厚声)")
      )
      (libsource (lib "easyedapro") (part "0603WAF3132T5E"))
    )
    (comp (ref "R36")
      (value "470kΩ")
      (footprint "easyedapro:R0603")
      (description "电阻类型:厚膜电阻;阻值:470kΩ;精度:±1%;功率:100mW;工作电压:75V;温度系数:±100ppm/°C;")
      (fields (field (name "Manufacturer Part") "FRC0603F4703TS") (field (name "Manufacturer") "FOJAN(富捷)"))
      (libsource (lib "easyedapro") (part "FRC0603F4703TS"))
    )
    (comp (ref "SW1")
      (value "KH-6X6X5H-STM")
      (footprint "easyedapro:SW-SMD_4P-L6.0-W6.0-P4.50-LS9.0_H5.0")
      (description "电路结构:单刀单掷;按钮形状:圆形按钮;安装方式:立贴;开关长度:6mm;开关宽度:6mm;开关高度:5mm;带支架:不带;触点电流:50mA;额定电压(DC):12V;机械寿命:8万次;")
      (fields (field (name "Manufacturer") "kinghelm(金航标)"))
      (libsource (lib "easyedapro") (part "KH-6X6X5H-STM"))
    )
    (comp (ref "SW2")
      (value "KH-6X6X5H-STM")
      (footprint "easyedapro:SW-SMD_4P-L6.0-W6.0-P4.50-LS9.0_H5.0")
      (description "电路结构:单刀单掷;按钮形状:圆形按钮;安装方式:立贴;开关长度:6mm;开关宽度:6mm;开关高度:5mm;带支架:不带;触点电流:50mA;额定电压(DC):12V;机械寿命:8万次;")
      (fields (field (name "Manufacturer") "kinghelm(金航标)"))
      (libsource (lib "easyedapro") (part "KH-6X6X5H-STM"))
    )
    (comp (ref "SW3")
      (value "KH-6X6X5H-STM")
      (footprint "easyedapro:SW-SMD_4P-L6.0-W6.0-P4.50-LS9.0_H5.0")
      (description "电路结构:单刀单掷;按钮形状:圆形按钮;安装方式:立贴;开关长度:6mm;开关宽度:6mm;开关高度:5mm;带支架:不带;触点电流:50mA;额定电压(DC):12V;机械寿命:8万次;")
      (fields (field (name "Manufacturer") "kinghelm(金航标)"))
      (libsource (lib "easyedapro") (part "KH-6X6X5H-STM"))
    )
    (comp (ref "U31")
      (value "ME6211C30M5G-N")
      (footprint "easyedapro:SOT-23-5_L2.9-W1.6-P0.95-LS2.8-BL")
      (description "输出类型:固定;最大输入电压:6V;输出电压:3V;最大输出电流:500mA;电源纹波抑制比(PSRR):-;输出极性:正极;")
      (fields (field (name "Manufacturer") "MICRONE(南京微盟)"))
      (libsource (lib "easyedapro") (part "ME6211C30M5G-N"))
    )
    (comp (ref "U34")
      (value "TJA1051T/3/1J")
      (footprint "easyedapro:SOIC-8_L4.9-W3.9-P1.27-LS6.0-BL")
      (description "类型:-;数据速率:5Mbps;")
      (fields (field (name "Manufacturer") "NXP(恩智浦)"))
      (libsource (lib "easyedapro") (part "TJA1051T/3/1J"))
    )
    (comp (ref "U36")
      (value "HX SS12D07VG5")
      (footprint "easyedapro:SW-TH_SS12D07VG3")
      (description "电路结构:单刀双掷;安装方式:直插;开关颜色:黑色;额定电流:300mA;额定电压:50V;工作寿命:1万次;")
      (fields (field (name "Manufacturer") "hanxia(韩下)"))
      (libsource (lib "easyedapro") (part "HX SS12D07VG5"))
    )
    (comp (ref "U37")
      (value "CP2104-F03-GMR")
      (footprint "easyedapro:QFN-24_L4.0-W4.0-P0.50-BL-EP2.7")
      (description "应用功能:USB转UART;接口协议:-;数据速率:2Mbps;")
      (fields (field (name "Manufacturer") "SKYWORKS/SILICON LABS(芯科)"))
      (libsource (lib "easyedapro") (part "CP2104-F03-GM"))
    )
    (comp (ref "U38")
      (value "MHT192WDT-GOLD")
      (footprint "easyedapro:LED0603-RD-YELLOW")
      (description "发光颜色:黄色;功率:60mW;正向电流:5mA;主波长:-;二极管配置:-;透镜颜色:雾状黄透镜;色温:-;发光角度:130°;载带方式:-;工作温度:-40°C~+85°C;")
      (fields (field (name "Manufacturer") "MEIHUA(美华)"))
      (libsource (lib "easyedapro") (part "MHT192WDT-GOLD"))
    )
    (comp (ref "U39")
      (value "2601-1103")
      (footprint "easyedapro:CONN-TH_6P-P3.50_2601-1103")
      (description "PCB 接线端子; 操作手柄; 1.5 mm2; 焊针间距 3.5 mm; 3极; 推入式笼夹; 1,50 mm2; 灰色")
      (fields (field (name "Manufacturer") "WAGO(万可)"))
      (libsource (lib "easyedapro") (part "2601-1103"))
    )
    (comp (ref "U40")
      (value "ME6211C30M5G-N")
      (footprint "easyedapro:SOT-23-5_L2.9-W1.6-P0.95-LS2.8-BL")
      (description "输出类型:固定;最大输入电压:6V;输出电压:3V;最大输出电流:500mA;电源纹波抑制比(PSRR):-;输出极性:正极;")
      (fields (field (name "Manufacturer") "MICRONE(南京微盟)"))
      (libsource (lib "easyedapro") (part "ME6211C30M5G-N"))
    )
    (comp (ref "U41")
      (value "ESP32-WROOM-32D-N4")
      (footprint "easyedapro:WIFIM-SMD_39P-L25.5-W18.0-P1.27-BL")
      (description "ESP32-WROOM-32D 集成 ESP32-D0WD，功能强大，用途广泛，可以用于低功耗传感器网络和要求极高的任务，例如语音编码、音频流和 MP3 解码等。")
      (fields (field (name "Manufacturer") "ESPRESSIF(乐鑫)"))
      (libsource (lib "easyedapro") (part "ESP32-WROOM-32D"))
    )
    (comp (ref "U42")
      (value "ME6211C30M5G-N")
      (footprint "easyedapro:SOT-23-5_L2.9-W1.6-P0.95-LS2.8-BL")
      (description "输出类型:固定;最大输入电压:6V;输出电压:3V;最大输出电流:500mA;电源纹波抑制比(PSRR):-;输出极性:正极;")
      (fields (field (name "Manufacturer") "MICRONE(南京微盟)"))
      (libsource (lib "easyedapro") (part "ME6211C30M5G-N"))
    )
    (comp (ref "U43")
      (value "TPS5450MDDAREP")
      (footprint "easyedapro:POWERPAD-SO-8_L4.9-W3.9-P1.27-LS6.0-BL-EP")
      (description "功能类型:降压型;输出类型:可调;工作电压:5.5V~36V;输出电压:1.221V~32.04V;输出电流:5A;")
      (fields (field (name "Manufacturer") "TI(德州仪器)"))
      (libsource (lib "easyedapro") (part "TPS5450MDDAREP"))
    )
    (comp (ref "USB1")
      (value "TYPE-C 16PIN 2MD(073)")
      (footprint "easyedapro:USB-C-SMD_TYPE-C-6PIN-2MD-073")
      (description "连接器类型:Type-C;协议标准:USB 3.1;公母:母;安装方式:卧贴;触点数量:16P;端口数量:1;额定电流 - 电源:3A;工作温度:-25°C~+85°C;")
      (fields (field (name "Manufacturer") "SHOU HAN(首韩)"))
      (libsource (lib "easyedapro") (part "TYPE-C 16PIN 2MD(073)"))
    )
  )
  (nets
    (net (code "1") (name "+5V") (class "Default")
      (node (ref "C1") (pin "1") (pinfunction "1_1") (pintype "unspecified"))
      (node (ref "C2") (pin "1") (pinfunction "1_1") (pintype "unspecified"))
      (node (ref "C3") (pin "1") (pinfunction "1_1") (pintype "unspecified"))
      (node (ref "C351") (pin "2") (pinfunction "2_2") (pintype "unspecified"))
      (node (ref "C353") (pin "2") (pinfunction "2_2") (pintype "unspecified"))
      (node (ref "C355") (pin "2") (pinfunction "2_2") (pintype "unspecified"))
      (node (ref "C356") (pin "2") (pinfunction "2_2") (pintype "unspecified"))
      (node (ref "C369") (pin "2") (pinfunction "2_2") (pintype "unspecified"))
      (node (ref "C371") (pin "2") (pinfunction "2_2") (pintype "unspecified"))
      (node (ref "C374") (pin "2") (pinfunction "2_2") (pintype "unspecified"))
      (node (ref "C376") (pin "2") (pinfunction "2_2") (pintype "unspecified"))
      (node (ref "D2") (pin "2") (pinfunction "C_2") (pintype "unspecified"))
      (node (ref "D3") (pin "1") (pinfunction "C_1") (pintype "unspecified"))
      (node (ref "D7") (pin "1") (pinfunction "K_1") (pintype "input"))
      (node (ref "H14") (pin "1") (pinfunction "1_1") (pintype "unspecified"))
      (node (ref "K1") (pin "5") (pinfunction "~_5") (pintype "unspecified"))
      (node (ref "R18") (pin "1") (pinfunction "1_1") (pintype "input"))
      (node (ref "R36") (pin "2") (pinfunction "2_2") (pintype "unspecified"))
      (node (ref "U31") (pin "1") (pinfunction "VIN_1") (pintype "unspecified"))
      (node (ref "U31") (pin "3") (pinfunction "CE_3") (pintype "unspecified"))
      (node (ref "U34") (pin "3") (pinfunction "VCC_3") (pintype "unspecified"))
      (node (ref "U40") (pin "1") (pinfunction "VIN_1") (pintype "unspecified"))
      (node (ref "U40") (pin "3") (pinfunction "CE_3") (pintype "unspecified"))
      (node (ref "U42") (pin "1") (pinfunction "VIN_1") (pintype "unspecified"))
      (node (ref "U42") (pin "3") (pinfunction "CE_3") (pintype "unspecified"))
    )
    (net (code "2") (name "/ADC") (class "Default")
      (node (ref "H17") (pin "1") (pinfunction "1_1") (pintype "unspecified"))
      (node (ref "R31") (pin "2") (pinfunction "2_2") (pintype "unspecified"))
      (node (ref "R32") (pin "2") (pinfunction "2_2") (pintype "input"))
    )
    (net (code "3") (name "/AUX_CAN_CS") (class "Default")
      (node (ref "H11") (pin "3") (pinfunction "3_3") (pintype "unspecified"))
      (node (ref "H14") (pin "18") (pinfunction "18_18") (pintype "unspecified"))
      (node (ref "U41") (pin "11") (pinfunction "IO26_11") (pintype "unspecified"))
    )
    (net (code "4") (name "/AUX_CAN_INT") (class "Default")
      (node (ref "H11") (pin "7") (pinfunction "7_7") (pintype "unspecified"))
      (node (ref "H14") (pin "20") (pinfunction "20_20") (pintype "unspecified"))
      (node (ref "U41") (pin "6") (pinfunction "IO34_6") (pintype "unspecified"))
    )
    (net (code "5") (name "/CAN_H") (class "Default")
      (node (ref "CN1") (pin "3") (pinfunction "3_3") (pintype "unspecified"))
      (node (ref "CN1") (pin "5") (pinfunction "5_5") (pintype "unspecified"))
      (node (ref "U34") (pin "7") (pinfunction "CANH_7") (pintype "unspecified"))
      (node (ref "U36") (pin "1") (pinfunction "1_1") (pintype "unspecified"))
    )
    (net (code "6") (name "/CAN_L") (class "Default")
      (node (ref "CN1") (pin "4") (pinfunction "4_4") (pintype "unspecified"))
      (node (ref "CN1") (pin "6") (pinfunction "6_6") (pintype "unspecified"))
      (node (ref "R30") (pin "2") (pinfunction "2_2") (pintype "input"))
      (node (ref "U34") (pin "6") (pinfunction "CANL_6") (pintype "unspecified"))
    )
    (net (code "7") (name "/CAN_RX") (class "Default")
      (node (ref "H14") (pin "24") (pinfunction "24_24") (pintype "unspecified"))
      (node (ref "U34") (pin "4") (pinfunction "RXD_4") (pintype "unspecified"))
      (node (ref "U41") (pin "29") (pinfunction "IO5_29") (pintype "unspecified"))
    )
    (net (code "8") (name "/CAN_TX") (class "Default")
      (node (ref "H14") (pin "23") (pinfunction "23_23") (pintype "unspecified"))
      (node (ref "U34") (pin "1") (pinfunction "TXD_1") (pintype "unspecified"))
      (node (ref "U41") (pin "26") (pinfunction "IO4_26") (pintype "unspecified"))
    )
    (net (code "9") (name "/DN") (class "Default")
      (node (ref "D1") (pin "3") (pinfunction "I/O2_3") (pintype "unspecified"))
      (node (ref "H16") (pin "3") (pinfunction "3_3") (pintype "unspecified"))
      (node (ref "USB1") (pin "5") (pinfunction "DN2_5") (pintype "unspecified"))
      (node (ref "USB1") (pin "7") (pinfunction "DN1_7") (pintype "unspecified"))
    )
    (net (code "10") (name "/DP") (class "Default")
      (node (ref "D1") (pin "1") (pinfunction "I/O1_1") (pintype "unspecified"))
      (node (ref "H16") (pin "2") (pinfunction "2_2") (pintype "unspecified"))
      (node (ref "USB1") (pin "6") (pinfunction "DP1_6") (pintype "unspecified"))
      (node (ref "USB1") (pin "8") (pinfunction "DP2_8") (pintype "unspecified"))
    )
    (net (code "11") (name "/DTR") (class "Default")
      (node (ref "H13") (pin "2") (pinfunction "2_2") (pintype "unspecified"))
      (node (ref "Q1") (pin "1") (pinfunction "E_1") (pintype "unspecified"))
      (node (ref "Q1") (pin "5") (pinfunction "B_5") (pintype "unspecified"))
      (node (ref "U37") (pin "23") (pinfunction "DTR_23") (pintype "unspecified"))
    )
    (net (code "12") (name "/EN") (class "Default")
      (node (ref "C10") (pin "1") (pinfunction "1_1") (pintype "unspecified"))
      (node (ref "C380") (pin "1") (pinfunction "1_1") (pintype "unspecified"))
      (node (ref "H12") (pin "2") (pinfunction "2_2") (pintype "unspecified"))
      (node (ref "Q1") (pin "4") (pinfunction "E_4") (pintype "unspecified"))
      (node (ref "R25") (pin "2") (pinfunction "2_2") (pintype "input"))
      (node (ref "R9") (pin "1") (pinfunction "1_1") (pintype "input"))
      (node (ref "SW2") (pin "3") (pinfunction "3_3") (pintype "unspecified"))
      (node (ref "SW2") (pin "4") (pinfunction "4_4") (pintype "unspecified"))
      (node (ref "U41") (pin "3") (pinfunction "EN_3") (pintype "unspecified"))
    )
    (net (code "13") (name "/FB") (class "Default")
      (node (ref "R34") (pin "2") (pinfunction "2_2") (pintype "input"))
      (node (ref "R35") (pin "1") (pinfunction "1_1") (pintype "unspecified"))
      (node (ref "U43") (pin "4") (pinfunction "VSENSE_4") (pintype "unspecified"))
    )
    (net (code "14") (name "/IO0") (class "Default")
      (node (ref "C11") (pin "1") (pinfunction "1_1") (pintype "unspecified"))
      (node (ref "H12") (pin "4") (pinfunction "4_4") (pintype "unspecified"))
      (node (ref "Q1") (pin "6") (pinfunction "C_6") (pintype "unspecified"))
      (node (ref "R10") (pin "1") (pinfunction "1_1") (pintype "input"))
      (node (ref "SW3") (pin "3") (pinfunction "3_3") (pintype "unspecified"))
      (node (ref "SW3") (pin "4") (pinfunction "4_4") (pintype "unspecified"))
      (node (ref "U41") (pin "25") (pinfunction "IO0_25") (pintype "unspecified"))
    )
    (net (code "15") (name "/IO2") (class "Default")
      (node (ref "H15") (pin "1") (pinfunction "1_1") (pintype "unspecified"))
      (node (ref "U41") (pin "24") (pinfunction "IO2_24") (pintype "unspecified"))
    )
    (net (code "16") (name "/IO12") (class "Default")
      (node (ref "H14") (pin "16") (pinfunction "16_16") (pintype "unspecified"))
      (node (ref "U41") (pin "14") (pinfunction "IO12_14") (pintype "unspecified"))
    )
    (net (code "17") (name "/IO16") (class "Default")
      (node (ref "H14") (pin "14") (pinfunction "14_14") (pintype "unspecified"))
      (node (ref "U41") (pin "27") (pinfunction "IO16_27") (pintype "unspecified"))
    )
    (net (code "18") (name "/IO35") (class "Default")
      (node (ref "H14") (pin "13") (pinfunction "13_13") (pintype "unspecified"))
      (node (ref "H8") (pin "3") (pinfunction "3_3") (pintype "unspecified"))
      (node (ref "U41") (pin "7") (pinfunction "IO35_7") (pintype "unspecified"))
    )
    (net (code "19") (name "/LED_B") (class "Default")
      (node (ref "H14") (pin "10") (pinfunction "10_10") (pintype "unspecified"))
      (node (ref "R14") (pin "1") (pinfunction "1_1") (pintype "input"))
      (node (ref "U41") (pin "13") (pinfunction "IO14_13") (pintype "unspecified"))
    )
    (net (code "20") (name "/LED_G") (class "Default")
      (node (ref "H14") (pin "8") (pinfunction "8_8") (pintype "unspecified"))
      (node (ref "R13") (pin "1") (pinfunction "1_1") (pintype "input"))
      (node (ref "U41") (pin "23") (pinfunction "IO15_23") (pintype "unspecified"))
    )
    (net (code "21") (name "/LED_R") (class "Default")
      (node (ref "H14") (pin "9") (pinfunction "9_9") (pintype "unspecified"))
      (node (ref "R12") (pin "1") (pinfunction "1_1") (pintype "input"))
      (node (ref "U41") (pin "16") (pinfunction "IO13_16") (pintype "unspecified"))
    )
    (net (code "22") (name "/MISO") (class "Default")
      (node (ref "H10") (pin "5") (pinfunction "5_5") (pintype "unspecified"))
      (node (ref "H11") (pin "4") (pinfunction "4_4") (pintype "unspecified"))
      (node (ref "H14") (pin "21") (pinfunction "21_21") (pintype "unspecified"))
      (node (ref "H9") (pin "5") (pinfunction "5_5") (pintype "unspecified"))
      (node (ref "U41") (pin "31") (pinfunction "IO19_31") (pintype "unspecified"))
    )
    (net (code "23") (name "/MOSI") (class "Default")
      (node (ref "H10") (pin "6") (pinfunction "6_6") (pintype "unspecified"))
      (node (ref "H11") (pin "5") (pinfunction "5_5") (pintype "unspecified"))
      (node (ref "H14") (pin "22") (pinfunction "22_22") (pintype "unspecified"))
      (node (ref "H9") (pin "6") (pinfunction "6_6") (pintype "unspecified"))
      (node (ref "U41") (pin "37") (pinfunction "IO23_37") (pintype "unspecified"))
    )
    (net (code "24") (name "/RELAY") (class "Default")
      (node (ref "H14") (pin "12") (pinfunction "12_12") (pintype "unspecified"))
      (node (ref "R20") (pin "1") (pinfunction "1_1") (pintype "input"))
      (node (ref "U41") (pin "10") (pinfunction "IO25_10") (pintype "unspecified"))
    )
    (net (code "25") (name "/RFID0_SS") (class "Default")
      (node (ref "H14") (pin "19") (pinfunction "19_19") (pintype "unspecified"))
      (node (ref "H9") (pin "8") (pinfunction "8_8") (pintype "unspecified"))
      (node (ref "U41") (pin "8") (pinfunction "IO32_8") (pintype "unspecified"))
    )
    (net (code "26") (name "/RFID1_SS") (class "Default")
      (node (ref "H10") (pin "8") (pinfunction "8_8") (pintype "unspecified"))
      (node (ref "H14") (pin "15") (pinfunction "15_15") (pintype "unspecified"))
      (node (ref "U41") (pin "9") (pinfunction "IO33_9") (pintype "unspecified"))
    )
    (net (code "27") (name "/RFID_RST") (class "Default")
      (node (ref "H10") (pin "2") (pinfunction "2_2") (pintype "unspecified"))
      (node (ref "H14") (pin "17") (pinfunction "17_17") (pintype "unspecified"))
      (node (ref "H9") (pin "2") (pinfunction "2_2") (pintype "unspecified"))
      (node (ref "U41") (pin "12") (pinfunction "IO27_12") (pintype "unspecified"))
    )
    (net (code "28") (name "/RTS") (class "Default")
      (node (ref "H13") (pin "1") (pinfunction "1_1") (pintype "unspecified"))
      (node (ref "Q1") (pin "2") (pinfunction "B_2") (pintype "unspecified"))
      (node (ref "Q1") (pin "3") (pinfunction "C_3") (pintype "unspecified"))
      (node (ref "U37") (pin "19") (pinfunction "RTS_19") (pintype "unspecified"))
    )
    (net (code "29") (name "/RX") (class "Default")
      (node (ref "H13") (pin "3") (pinfunction "3_3") (pintype "unspecified"))
      (node (ref "R5") (pin "2") (pinfunction "2_2") (pintype "input"))
      (node (ref "U41") (pin "35") (pinfunction "TXD0_35") (pintype "unspecified"))
    )
    (net (code "30") (name "/SCK") (class "Default")
      (node (ref "H10") (pin "7") (pinfunction "7_7") (pintype "unspecified"))
      (node (ref "H11") (pin "6") (pinfunction "6_6") (pintype "unspecified"))
      (node (ref "H14") (pin "6") (pinfunction "6_6") (pintype "unspecified"))
      (node (ref "H9") (pin "7") (pinfunction "7_7") (pintype "unspecified"))
      (node (ref "U41") (pin "30") (pinfunction "IO18_30") (pintype "unspecified"))
    )
    (net (code "31") (name "/SCL") (class "Default")
      (node (ref "H14") (pin "5") (pinfunction "5_5") (pintype "unspecified"))
      (node (ref "H6") (pin "4") (pinfunction "4_4") (pintype "unspecified"))
      (node (ref "H7") (pin "4") (pinfunction "4_4") (pintype "unspecified"))
      (node (ref "R21") (pin "2") (pinfunction "2_2") (pintype "input"))
      (node (ref "U41") (pin "36") (pinfunction "IO22_36") (pintype "unspecified"))
    )
    (net (code "32") (name "/SDA") (class "Default")
      (node (ref "H14") (pin "7") (pinfunction "7_7") (pintype "unspecified"))
      (node (ref "H6") (pin "3") (pinfunction "3_3") (pintype "unspecified"))
      (node (ref "H7") (pin "3") (pinfunction "3_3") (pintype "unspecified"))
      (node (ref "R22") (pin "2") (pinfunction "2_2") (pintype "input"))
      (node (ref "U41") (pin "33") (pinfunction "IO21_33") (pintype "unspecified"))
    )
    (net (code "33") (name "/SW") (class "Default")
      (node (ref "C9") (pin "1") (pinfunction "1_1") (pintype "unspecified"))
      (node (ref "H14") (pin "11") (pinfunction "11_11") (pintype "unspecified"))
      (node (ref "R8") (pin "1") (pinfunction "1_1") (pintype "input"))
      (node (ref "SW1") (pin "3") (pinfunction "3_3") (pintype "unspecified"))
      (node (ref "SW1") (pin "4") (pinfunction "4_4") (pintype "unspecified"))
      (node (ref "U41") (pin "28") (pinfunction "IO17_28") (pintype "unspecified"))
    )
    (net (code "34") (name "/TX") (class "Default")
      (node (ref "H13") (pin "4") (pinfunction "4_4") (pintype "unspecified"))
      (node (ref "R4") (pin "2") (pinfunction "2_2") (pintype "input"))
      (node (ref "U41") (pin "34") (pinfunction "RXD0_34") (pintype "unspecified"))
    )
    (net (code "35") (name "/USB5V") (class "Default")
      (node (ref "D2") (pin "1") (pinfunction "A_1") (pintype "unspecified"))
      (node (ref "D8") (pin "1") (pinfunction "A_1") (pintype "unspecified"))
      (node (ref "H16") (pin "4") (pinfunction "4_4") (pintype "unspecified"))
      (node (ref "USB1") (pin "11") (pinfunction "VBUS_11") (pintype "unspecified"))
      (node (ref "USB1") (pin "2") (pinfunction "VBUS_2") (pintype "unspecified"))
    )
    (net (code "36") (name "3.3_SENSOR") (class "Default")
      (node (ref "C363") (pin "1") (pinfunction "1_1") (pintype "unspecified"))
      (node (ref "C364") (pin "1") (pinfunction "1_1") (pintype "unspecified"))
      (node (ref "C370") (pin "2") (pinfunction "2_2") (pintype "unspecified"))
      (node (ref "C372") (pin "2") (pinfunction "2_2") (pintype "unspecified"))
      (node (ref "H10") (pin "1") (pinfunction "1_1") (pintype "unspecified"))
      (node (ref "H11") (pin "1") (pinfunction "1_1") (pintype "unspecified"))
      (node (ref "H6") (pin "2") (pinfunction "2_2") (pintype "unspecified"))
      (node (ref "H7") (pin "2") (pinfunction "2_2") (pintype "unspecified"))
      (node (ref "H8") (pin "2") (pinfunction "2_2") (pintype "unspecified"))
      (node (ref "H9") (pin "1") (pinfunction "1_1") (pintype "unspecified"))
      (node (ref "R21") (pin "1") (pinfunction "1_1") (pintype "input"))
      (node (ref "R22") (pin "1") (pinfunction "1_1") (pintype "input"))
      (node (ref "R23") (pin "2") (pinfunction "2_2") (pintype "input"))
      (node (ref "U40") (pin "5") (pinfunction "VOUT_5") (pintype "unspecified"))
    )
    (net (code "37") (name "3V3") (class "Default")
      (node (ref "C352") (pin "2") (pinfunction "2_2") (pintype "unspecified"))
      (node (ref "C354") (pin "2") (pinfunction "2_2") (pintype "unspecified"))
      (node (ref "C357") (pin "2") (pinfunction "2_2") (pintype "unspecified"))
      (node (ref "C358") (pin "2") (pinfunction "2_2") (pintype "unspecified"))
      (node (ref "H12") (pin "1") (pinfunction "1_1") (pintype "unspecified"))
      (node (ref "H14") (pin "2") (pinfunction "2_2") (pintype "unspecified"))
      (node (ref "R10") (pin "2") (pinfunction "2_2") (pintype "input"))
      (node (ref "R11") (pin "2") (pinfunction "2_2") (pintype "input"))
      (node (ref "R8") (pin "2") (pinfunction "2_2") (pintype "input"))
      (node (ref "R9") (pin "2") (pinfunction "2_2") (pintype "input"))
      (node (ref "U31") (pin "5") (pinfunction "VOUT_5") (pintype "unspecified"))
      (node (ref "U34") (pin "5") (pinfunction "VIO_5") (pintype "unspecified"))
    )
    (net (code "38") (name "3V3_POWER") (class "Default")
      (node (ref "C373") (pin "2") (pinfunction "2_2") (pintype "unspecified"))
      (node (ref "C375") (pin "2") (pinfunction "2_2") (pintype "unspecified"))
      (node (ref "C377") (pin "1") (pinfunction "1_1") (pintype "unspecified"))
      (node (ref "C378") (pin "1") (pinfunction "1_1") (pintype "unspecified"))
      (node (ref "C379") (pin "1") (pinfunction "1_1") (pintype "unspecified"))
      (node (ref "R24") (pin "2") (pinfunction "2_2") (pintype "input"))
      (node (ref "R25") (pin "1") (pinfunction "1_1") (pintype "input"))
      (node (ref "U41") (pin "2") (pinfunction "VDD33_2") (pintype "unspecified"))
      (node (ref "U42") (pin "5") (pinfunction "VOUT_5") (pintype "unspecified"))
    )
    (net (code "39") (name "CP210-5V") (class "Default")
      (node (ref "C361") (pin "2") (pinfunction "2_2") (pintype "unspecified"))
      (node (ref "C362") (pin "2") (pinfunction "2_2") (pintype "unspecified"))
      (node (ref "D1") (pin "5") (pinfunction "VBUS_5") (pintype "unspecified"))
      (node (ref "D8") (pin "2") (pinfunction "C_2") (pintype "unspecified"))
      (node (ref "U37") (pin "7") (pinfunction "REGIN_7") (pintype "unspecified"))
      (node (ref "U37") (pin "8") (pinfunction "VBUS_8") (pintype "unspecified"))
    )
    (net (code "40") (name "GND") (class "Default")
      (node (ref "C1") (pin "2") (pinfunction "2_2") (pintype "unspecified"))
      (node (ref "C10") (pin "2") (pinfunction "2_2") (pintype "unspecified"))
      (node (ref "C11") (pin "2") (pinfunction "2_2") (pintype "unspecified"))
      (node (ref "C2") (pin "2") (pinfunction "2_2") (pintype "unspecified"))
      (node (ref "C3") (pin "2") (pinfunction "2_2") (pintype "unspecified"))
      (node (ref "C351") (pin "1") (pinfunction "1_1") (pintype "unspecified"))
      (node (ref "C352") (pin "1") (pinfunction "1_1") (pintype "unspecified"))
      (node (ref "C353") (pin "1") (pinfunction "1_1") (pintype "unspecified"))
      (node (ref "C354") (pin "1") (pinfunction "1_1") (pintype "unspecified"))
      (node (ref "C355") (pin "1") (pinfunction "1_1") (pintype "unspecified"))
      (node (ref "C356") (pin "1") (pinfunction "1_1") (pintype "unspecified"))
      (node (ref "C357") (pin "1") (pinfunction "1_1") (pintype "unspecified"))
      (node (ref "C358") (pin "1") (pinfunction "1_1") (pintype "unspecified"))
      (node (ref "C359") (pin "1") (pinfunction "1_1") (pintype "unspecified"))
      (node (ref "C360") (pin "1") (pinfunction "1_1") (pintype "unspecified"))
      (node (ref "C361") (pin "1") (pinfunction "1_1") (pintype "unspecified"))
      (node (ref "C362") (pin "1") (pinfunction "1_1") (pintype "unspecified"))
      (node (ref "C363") (pin "2") (pinfunction "2_2") (pintype "unspecified"))
      (node (ref "C364") (pin "2") (pinfunction "2_2") (pintype "unspecified"))
      (node (ref "C369") (pin "1") (pinfunction "1_1") (pintype "unspecified"))
      (node (ref "C370") (pin "1") (pinfunction "1_1") (pintype "unspecified"))
      (node (ref "C371") (pin "1") (pinfunction "1_1") (pintype "unspecified"))
      (node (ref "C372") (pin "1") (pinfunction "1_1") (pintype "unspecified"))
      (node (ref "C373") (pin "1") (pinfunction "1_1") (pintype "unspecified"))
      (node (ref "C374") (pin "1") (pinfunction "1_1") (pintype "unspecified"))
      (node (ref "C375") (pin "1") (pinfunction "1_1") (pintype "unspecified"))
      (node (ref "C376") (pin "1") (pinfunction "1_1") (pintype "unspecified"))
      (node (ref "C377") (pin "2") (pinfunction "2_2") (pintype "unspecified"))
      (node (ref "C378") (pin "2") (pinfunction "2_2") (pintype "unspecified"))
      (node (ref "C379") (pin "2") (pinfunction "2_2") (pintype "unspecified"))
      (node (ref "C380") (pin "2") (pinfunction "2_2") (pintype "unspecified"))
      (node (ref "C382") (pin "1") (pinfunction "1_1") (pintype "unspecified"))
      (node (ref "C383") (pin "1") (pinfunction "1_1") (pintype "unspecified"))
      (node (ref "C384") (pin "1") (pinfunction "1_1") (pintype "input"))
      (node (ref "C385") (pin "1") (pinfunction "1_1") (pintype "unspecified"))
      (node (ref "C386") (pin "1") (pinfunction "1_1") (pintype "unspecified"))
      (node (ref "C387") (pin "1") (pinfunction "1_1") (pintype "unspecified"))
      (node (ref "C388") (pin "1") (pinfunction "1_1") (pintype "unspecified"))
      (node (ref "C390") (pin "1") (pinfunction "1_1") (pintype "unspecified"))
      (node (ref "C6") (pin "1") (pinfunction "1_1") (pintype "unspecified"))
      (node (ref "C9") (pin "2") (pinfunction "2_2") (pintype "unspecified"))
      (node (ref "CN1") (pin "2") (pinfunction "2_2") (pintype "unspecified"))
      (node (ref "D1") (pin "2") (pinfunction "GND_2") (pintype "unspecified"))
      (node (ref "D5") (pin "2") (pinfunction "A_2") (pintype "input"))
      (node (ref "D6") (pin "1") (pinfunction "A_1") (pintype "input"))
      (node (ref "H10") (pin "3") (pinfunction "3_3") (pintype "unspecified"))
      (node (ref "H11") (pin "2") (pinfunction "2_2") (pintype "unspecified"))
      (node (ref "H12") (pin "3") (pinfunction "3_3") (pintype "unspecified"))
      (node (ref "H14") (pin "3") (pinfunction "3_3") (pintype "unspecified"))
      (node (ref "H14") (pin "4") (pinfunction "4_4") (pintype "unspecified"))
      (node (ref "H16") (pin "1") (pinfunction "1_1") (pintype "unspecified"))
      (node (ref "H17") (pin "2") (pinfunction "2_2") (pintype "unspecified"))
      (node (ref "H6") (pin "1") (pinfunction "1_1") (pintype "unspecified"))
      (node (ref "H7") (pin "1") (pinfunction "1_1") (pintype "unspecified"))
      (node (ref "H8") (pin "1") (pinfunction "1_1") (pintype "unspecified"))
      (node (ref "H9") (pin "3") (pinfunction "3_3") (pintype "unspecified"))
      (node (ref "LED1") (pin "4") (pinfunction "-_4") (pintype "unspecified"))
      (node (ref "LED1") (pin "5") (pinfunction "-_5") (pintype "unspecified"))
      (node (ref "LED1") (pin "6") (pinfunction "-_6") (pintype "unspecified"))
      (node (ref "LED白") (pin "1") (pinfunction "-_1") (pintype "input"))
      (node (ref "LED红") (pin "2") (pinfunction "-_2") (pintype "unspecified"))
      (node (ref "LED绿") (pin "1") (pinfunction "K_1") (pintype "unspecified"))
      (node (ref "LED蓝") (pin "2") (pinfunction "-_2") (pintype "unspecified"))
      (node (ref "Q2") (pin "2") (pinfunction "E_2") (pintype "unspecified"))
      (node (ref "R1") (pin "2") (pinfunction "2_2") (pintype "input"))
      (node (ref "R15") (pin "2") (pinfunction "2_2") (pintype "input"))
      (node (ref "R19") (pin "2") (pinfunction "2_2") (pintype "input"))
      (node (ref "R2") (pin "2") (pinfunction "2_2") (pintype "input"))
      (node (ref "R32") (pin "1") (pinfunction "1_1") (pintype "input"))
      (node (ref "R35") (pin "2") (pinfunction "2_2") (pintype "unspecified"))
      (node (ref "SW1") (pin "1") (pinfunction "1_1") (pintype "unspecified"))
      (node (ref "SW1") (pin "2") (pinfunction "2_2") (pintype "unspecified"))
      (node (ref "SW2") (pin "1") (pinfunction "1_1") (pintype "unspecified"))
      (node (ref "SW2") (pin "2") (pinfunction "2_2") (pintype "unspecified"))
      (node (ref "SW3") (pin "1") (pinfunction "1_1") (pintype "unspecified"))
      (node (ref "SW3") (pin "2") (pinfunction "2_2") (pintype "unspecified"))
      (node (ref "U31") (pin "2") (pinfunction "VSS_2") (pintype "unspecified"))
      (node (ref "U34") (pin "2") (pinfunction "GND_2") (pintype "unspecified"))
      (node (ref "U36") (pin "4") (pinfunction "4_4") (pintype "unspecified"))
      (node (ref "U36") (pin "5") (pinfunction "5_5") (pintype "unspecified"))
      (node (ref "U37") (pin "2") (pinfunction "GND_2") (pintype "unspecified"))
      (node (ref "U37") (pin "25") (pinfunction "EPAD_25") (pintype "unspecified"))
      (node (ref "U40") (pin "2") (pinfunction "VSS_2") (pintype "unspecified"))
      (node (ref "U41") (pin "1") (pinfunction "GND_1") (pintype "unspecified"))
      (node (ref "U41") (pin "15") (pinfunction "GND_15") (pintype "unspecified"))
      (node (ref "U41") (pin "38") (pinfunction "GND_38") (pintype "unspecified"))
      (node (ref "U41") (pin "39") (pinfunction "GND_39") (pintype "unspecified"))
      (node (ref "U42") (pin "2") (pinfunction "VSS_2") (pintype "unspecified"))
      (node (ref "U43") (pin "6") (pinfunction "GND_6") (pintype "unspecified"))
      (node (ref "U43") (pin "9") (pinfunction "EP_9") (pintype "unspecified"))
      (node (ref "USB1") (pin "1") (pinfunction "GND_1") (pintype "unspecified"))
      (node (ref "USB1") (pin "12") (pinfunction "GND_12") (pintype "unspecified"))
      (node (ref "USB1") (pin "13") (pinfunction "SHELL_13") (pintype "unspecified"))
      (node (ref "USB1") (pin "14") (pinfunction "SHELL_14") (pintype "unspecified"))
    )
    (net (code "41") (name "Net-(C390-Pad2)") (class "Default")
      (node (ref "C390") (pin "2") (pinfunction "2_2") (pintype "unspecified"))
      (node (ref "R36") (pin "1") (pinfunction "1_1") (pintype "unspecified"))
    )
    (net (code "42") (name "Net-(D3-A)") (class "Default")
      (node (ref "D3") (pin "2") (pinfunction "A_2") (pintype "unspecified"))
      (node (ref "K1") (pin "2") (pinfunction "~_2") (pintype "unspecified"))
      (node (ref "Q2") (pin "3") (pinfunction "C_3") (pintype "unspecified"))
      (node (ref "U38") (pin "1") (pinfunction "K_1") (pintype "unspecified"))
    )
    (net (code "43") (name "Net-(D5-K)") (class "Default")
      (node (ref "C389") (pin "1") (pinfunction "1_1") (pintype "unspecified"))
      (node (ref "D5") (pin "1") (pinfunction "K_1") (pintype "input"))
      (node (ref "L12") (pin "1") (pinfunction "1_1") (pintype "unspecified"))
      (node (ref "U43") (pin "8") (pinfunction "PH_8") (pintype "unspecified"))
    )
    (net (code "44") (name "Net-(D7-A)") (class "Default")
      (node (ref "C385") (pin "2") (pinfunction "2_2") (pintype "unspecified"))
      (node (ref "C386") (pin "2") (pinfunction "2_2") (pintype "unspecified"))
      (node (ref "C387") (pin "2") (pinfunction "2_2") (pintype "unspecified"))
      (node (ref "C388") (pin "2") (pinfunction "2_2") (pintype "unspecified"))
      (node (ref "D7") (pin "2") (pinfunction "A_2") (pintype "input"))
      (node (ref "L12") (pin "2") (pinfunction "2_2") (pintype "unspecified"))
      (node (ref "R34") (pin "1") (pinfunction "1_1") (pintype "input"))
    )
    (net (code "45") (name "Net-(K1-~-Pad1)") (class "Default")
      (node (ref "K1") (pin "1") (pinfunction "~_1") (pintype "unspecified"))
      (node (ref "U39") (pin "3") (pinfunction "3_3") (pintype "unspecified"))
      (node (ref "U39") (pin "4") (pinfunction "4_4") (pintype "unspecified"))
    )
    (net (code "46") (name "Net-(K1-~-Pad3)") (class "Default")
      (node (ref "K1") (pin "3") (pinfunction "~_3") (pintype "unspecified"))
      (node (ref "U39") (pin "5") (pinfunction "5_5") (pintype "unspecified"))
      (node (ref "U39") (pin "6") (pinfunction "6_6") (pintype "unspecified"))
    )
    (net (code "47") (name "Net-(K1-~-Pad4)") (class "Default")
      (node (ref "K1") (pin "4") (pinfunction "~_4") (pintype "unspecified"))
      (node (ref "U39") (pin "1") (pinfunction "1_1") (pintype "unspecified"))
      (node (ref "U39") (pin "2") (pinfunction "2_2") (pintype "unspecified"))
    )
    (net (code "48") (name "Net-(LED1-+-Pad1)") (class "Default")
      (node (ref "LED1") (pin "1") (pinfunction "+_1") (pintype "unspecified"))
      (node (ref "R12") (pin "2") (pinfunction "2_2") (pintype "input"))
    )
    (net (code "49") (name "Net-(LED1-+-Pad2)") (class "Default")
      (node (ref "LED1") (pin "2") (pinfunction "+_2") (pintype "unspecified"))
      (node (ref "R13") (pin "2") (pinfunction "2_2") (pintype "input"))
    )
    (net (code "50") (name "Net-(LED1-+-Pad3)") (class "Default")
      (node (ref "LED1") (pin "3") (pinfunction "+_3") (pintype "unspecified"))
      (node (ref "R14") (pin "2") (pinfunction "2_2") (pintype "input"))
    )
    (net (code "51") (name "Net-(LED白-+)") (class "Default")
      (node (ref "LED白") (pin "2") (pinfunction "+_2") (pintype "input"))
      (node (ref "R7") (pin "2") (pinfunction "2_2") (pintype "input"))
    )
    (net (code "52") (name "Net-(LED红-+)") (class "Default")
      (node (ref "LED红") (pin "1") (pinfunction "+_1") (pintype "unspecified"))
      (node (ref "R24") (pin "1") (pinfunction "1_1") (pintype "input"))
    )
    (net (code "53") (name "Net-(LED绿-A)") (class "Default")
      (node (ref "LED绿") (pin "2") (pinfunction "A_2") (pintype "unspecified"))
      (node (ref "R23") (pin "1") (pinfunction "1_1") (pintype "input"))
    )
    (net (code "54") (name "Net-(LED蓝-+)") (class "Default")
      (node (ref "LED蓝") (pin "1") (pinfunction "+_1") (pintype "unspecified"))
      (node (ref "R11") (pin "1") (pinfunction "1_1") (pintype "input"))
    )
    (net (code "55") (name "Net-(Q2-B)") (class "Default")
      (node (ref "Q2") (pin "1") (pinfunction "B_1") (pintype "unspecified"))
      (node (ref "R19") (pin "1") (pinfunction "1_1") (pintype "input"))
      (node (ref "R20") (pin "2") (pinfunction "2_2") (pintype "input"))
    )
    (net (code "56") (name "Net-(R30-Pad1)") (class "Default")
      (node (ref "R30") (pin "1") (pinfunction "1_1") (pintype "input"))
      (node (ref "U36") (pin "2") (pinfunction "2_2") (pintype "unspecified"))
    )
    (net (code "57") (name "Net-(U34-S)") (class "Default")
      (node (ref "R15") (pin "1") (pinfunction "1_1") (pintype "input"))
      (node (ref "U34") (pin "8") (pinfunction "S_8") (pintype "unspecified"))
    )
    (net (code "58") (name "Net-(U37-D+)") (class "Default")
      (node (ref "D1") (pin "6") (pinfunction "I/O1_6") (pintype "unspecified"))
      (node (ref "U37") (pin "3") (pinfunction "D+_3") (pintype "unspecified"))
    )
    (net (code "59") (name "Net-(U37-D-)") (class "Default")
      (node (ref "D1") (pin "4") (pinfunction "I/O2_4") (pintype "unspecified"))
      (node (ref "U37") (pin "4") (pinfunction "D-_4") (pintype "unspecified"))
    )
    (net (code "60") (name "Net-(U37-RST#)") (class "Default")
      (node (ref "R17") (pin "2") (pinfunction "2_2") (pintype "input"))
      (node (ref "U37") (pin "9") (pinfunction "RST#_9") (pintype "unspecified"))
    )
    (net (code "61") (name "Net-(U37-RXD)") (class "Default")
      (node (ref "R5") (pin "1") (pinfunction "1_1") (pintype "input"))
      (node (ref "U37") (pin "20") (pinfunction "RXD_20") (pintype "unspecified"))
    )
    (net (code "62") (name "Net-(U37-TXD)") (class "Default")
      (node (ref "R4") (pin "1") (pinfunction "1_1") (pintype "input"))
      (node (ref "U37") (pin "21") (pinfunction "TXD_21") (pintype "unspecified"))
    )
    (net (code "63") (name "Net-(U37-VPP)") (class "Default")
      (node (ref "C6") (pin "2") (pinfunction "2_2") (pintype "unspecified"))
      (node (ref "U37") (pin "16") (pinfunction "VPP_16") (pintype "unspecified"))
    )
    (net (code "64") (name "Net-(U38-A)") (class "Default")
      (node (ref "R18") (pin "2") (pinfunction "2_2") (pintype "input"))
      (node (ref "U38") (pin "2") (pinfunction "A_2") (pintype "unspecified"))
    )
    (net (code "65") (name "Net-(U43-BOOT)") (class "Default")
      (node (ref "C389") (pin "2") (pinfunction "2_2") (pintype "unspecified"))
      (node (ref "U43") (pin "1") (pinfunction "BOOT_1") (pintype "unspecified"))
    )
    (net (code "66") (name "Net-(USB1-CC1)") (class "Default")
      (node (ref "R2") (pin "1") (pinfunction "1_1") (pintype "input"))
      (node (ref "USB1") (pin "4") (pinfunction "CC1_4") (pintype "unspecified"))
    )
    (net (code "67") (name "Net-(USB1-CC2)") (class "Default")
      (node (ref "R1") (pin "1") (pinfunction "1_1") (pintype "input"))
      (node (ref "USB1") (pin "10") (pinfunction "CC2_10") (pintype "unspecified"))
    )
    (net (code "68") (name "VCC") (class "Default")
      (node (ref "C382") (pin "2") (pinfunction "2_2") (pintype "unspecified"))
      (node (ref "C383") (pin "2") (pinfunction "2_2") (pintype "unspecified"))
      (node (ref "C384") (pin "2") (pinfunction "2_2") (pintype "input"))
      (node (ref "CN1") (pin "1") (pinfunction "1_1") (pintype "unspecified"))
      (node (ref "D6") (pin "2") (pinfunction "K_2") (pintype "input"))
      (node (ref "R31") (pin "1") (pinfunction "1_1") (pintype "unspecified"))
      (node (ref "U43") (pin "7") (pinfunction "VIN_7") (pintype "unspecified"))
    )
    (net (code "69") (name "VDD") (class "Default")
      (node (ref "C359") (pin "2") (pinfunction "2_2") (pintype "unspecified"))
      (node (ref "C360") (pin "2") (pinfunction "2_2") (pintype "unspecified"))
      (node (ref "R17") (pin "1") (pinfunction "1_1") (pintype "input"))
      (node (ref "R7") (pin "1") (pinfunction "1_1") (pintype "input"))
      (node (ref "U37") (pin "5") (pinfunction "VIO_5") (pintype "unspecified"))
      (node (ref "U37") (pin "6") (pinfunction "VDD_6") (pintype "unspecified"))
    )
    (net (code "70") (name "unconnected-(H1-Pad1)") (class "Default")
      (node (ref "H1") (pin "1") (pinfunction "1_1") (pintype "input+no_connect"))
    )
    (net (code "71") (name "unconnected-(H2-Pad1)") (class "Default")
      (node (ref "H2") (pin "1") (pinfunction "1_1") (pintype "input+no_connect"))
    )
    (net (code "72") (name "unconnected-(H3-Pad1)") (class "Default")
      (node (ref "H3") (pin "1") (pinfunction "1_1") (pintype "input+no_connect"))
    )
    (net (code "73") (name "unconnected-(H4-Pad1)") (class "Default")
      (node (ref "H4") (pin "1") (pinfunction "1_1") (pintype "input+no_connect"))
    )
    (net (code "74") (name "unconnected-(H9-Pad4)") (class "Default")
      (node (ref "H9") (pin "4") (pinfunction "4_4") (pintype "unspecified+no_connect"))
    )
    (net (code "75") (name "unconnected-(H10-Pad4)") (class "Default")
      (node (ref "H10") (pin "4") (pinfunction "4_4") (pintype "unspecified+no_connect"))
    )
    (net (code "76") (name "unconnected-(U31-NC-Pad4)") (class "Default")
      (node (ref "U31") (pin "4") (pinfunction "NC_4") (pintype "unspecified+no_connect"))
    )
    (net (code "77") (name "unconnected-(U36-Pad3)") (class "Default")
      (node (ref "U36") (pin "3") (pinfunction "3_3") (pintype "unspecified+no_connect"))
    )
    (net (code "78") (name "unconnected-(U37-CTS-Pad18)") (class "Default")
      (node (ref "U37") (pin "18") (pinfunction "CTS_18") (pintype "unspecified+no_connect"))
    )
    (net (code "79") (name "unconnected-(U37-DCD-Pad24)") (class "Default")
      (node (ref "U37") (pin "24") (pinfunction "DCD_24") (pintype "unspecified+no_connect"))
    )
    (net (code "80") (name "unconnected-(U37-DSR-Pad22)") (class "Default")
      (node (ref "U37") (pin "22") (pinfunction "DSR_22") (pintype "unspecified+no_connect"))
    )
    (net (code "81") (name "unconnected-(U37-GPIO.0-Pad14)") (class "Default")
      (node (ref "U37") (pin "14") (pinfunction "GPIO.0_14") (pintype "unspecified+no_connect"))
    )
    (net (code "82") (name "unconnected-(U37-GPIO.1-Pad13)") (class "Default")
      (node (ref "U37") (pin "13") (pinfunction "GPIO.1_13") (pintype "unspecified+no_connect"))
    )
    (net (code "83") (name "unconnected-(U37-GPIO.2-Pad12)") (class "Default")
      (node (ref "U37") (pin "12") (pinfunction "GPIO.2_12") (pintype "unspecified+no_connect"))
    )
    (net (code "84") (name "unconnected-(U37-GPIO.3-Pad11)") (class "Default")
      (node (ref "U37") (pin "11") (pinfunction "GPIO.3_11") (pintype "unspecified+no_connect"))
    )
    (net (code "85") (name "unconnected-(U37-NC-Pad10)") (class "Default")
      (node (ref "U37") (pin "10") (pinfunction "NC_10") (pintype "unspecified+no_connect"))
    )
    (net (code "86") (name "unconnected-(U37-RI-Pad1)") (class "Default")
      (node (ref "U37") (pin "1") (pinfunction "RI_1") (pintype "unspecified+no_connect"))
    )
    (net (code "87") (name "unconnected-(U37-SUSPEND#-Pad15)") (class "Default")
      (node (ref "U37") (pin "15") (pinfunction "SUSPEND#_15") (pintype "unspecified+no_connect"))
    )
    (net (code "88") (name "unconnected-(U37-SUSPEND-Pad17)") (class "Default")
      (node (ref "U37") (pin "17") (pinfunction "SUSPEND_17") (pintype "unspecified+no_connect"))
    )
    (net (code "89") (name "unconnected-(U40-NC-Pad4)") (class "Default")
      (node (ref "U40") (pin "4") (pinfunction "NC_4") (pintype "unspecified+no_connect"))
    )
    (net (code "90") (name "unconnected-(U41-CLK-Pad20)") (class "Default")
      (node (ref "U41") (pin "20") (pinfunction "CLK_20") (pintype "unspecified+no_connect"))
    )
    (net (code "91") (name "unconnected-(U41-CMD-Pad19)") (class "Default")
      (node (ref "U41") (pin "19") (pinfunction "CMD_19") (pintype "unspecified+no_connect"))
    )
    (net (code "92") (name "unconnected-(U41-NC-Pad32)") (class "Default")
      (node (ref "U41") (pin "32") (pinfunction "NC_32") (pintype "unspecified+no_connect"))
    )
    (net (code "93") (name "unconnected-(U41-SD0-Pad21)") (class "Default")
      (node (ref "U41") (pin "21") (pinfunction "SD0_21") (pintype "unspecified+no_connect"))
    )
    (net (code "94") (name "unconnected-(U41-SD1-Pad22)") (class "Default")
      (node (ref "U41") (pin "22") (pinfunction "SD1_22") (pintype "unspecified+no_connect"))
    )
    (net (code "95") (name "unconnected-(U41-SD2-Pad17)") (class "Default")
      (node (ref "U41") (pin "17") (pinfunction "SD2_17") (pintype "unspecified+no_connect"))
    )
    (net (code "96") (name "unconnected-(U41-SD3-Pad18)") (class "Default")
      (node (ref "U41") (pin "18") (pinfunction "SD3_18") (pintype "unspecified+no_connect"))
    )
    (net (code "97") (name "unconnected-(U41-SENSOR_VN-Pad5)") (class "Default")
      (node (ref "U41") (pin "5") (pinfunction "SENSOR_VN_5") (pintype "unspecified+no_connect"))
    )
    (net (code "98") (name "unconnected-(U41-SENSOR_VP-Pad4)") (class "Default")
      (node (ref "U41") (pin "4") (pinfunction "SENSOR_VP_4") (pintype "unspecified+no_connect"))
    )
    (net (code "99") (name "unconnected-(U42-NC-Pad4)") (class "Default")
      (node (ref "U42") (pin "4") (pinfunction "NC_4") (pintype "unspecified+no_connect"))
    )
    (net (code "100") (name "unconnected-(U43-ENA-Pad5)") (class "Default")
      (node (ref "U43") (pin "5") (pinfunction "ENA_5") (pintype "unspecified+no_connect"))
    )
    (net (code "101") (name "unconnected-(U43-NC-Pad2)") (class "Default")
      (node (ref "U43") (pin "2") (pinfunction "NC_2") (pintype "unspecified+no_connect"))
    )
    (net (code "102") (name "unconnected-(U43-NC-Pad3)") (class "Default")
      (node (ref "U43") (pin "3") (pinfunction "NC_3") (pintype "unspecified+no_connect"))
    )
    (net (code "103") (name "unconnected-(USB1-SBU1-Pad9)") (class "Default")
      (node (ref "USB1") (pin "9") (pinfunction "SBU1_9") (pintype "unspecified+no_connect"))
    )
    (net (code "104") (name "unconnected-(USB1-SBU2-Pad3)") (class "Default")
      (node (ref "USB1") (pin "3") (pinfunction "SBU2_3") (pintype "unspecified+no_connect"))
    )
  )
)
